# Oscillator_Or_Joystick_Ambisonic_Pan-Rot.net
KiCad netlist of a schematic drawn in EAGLE
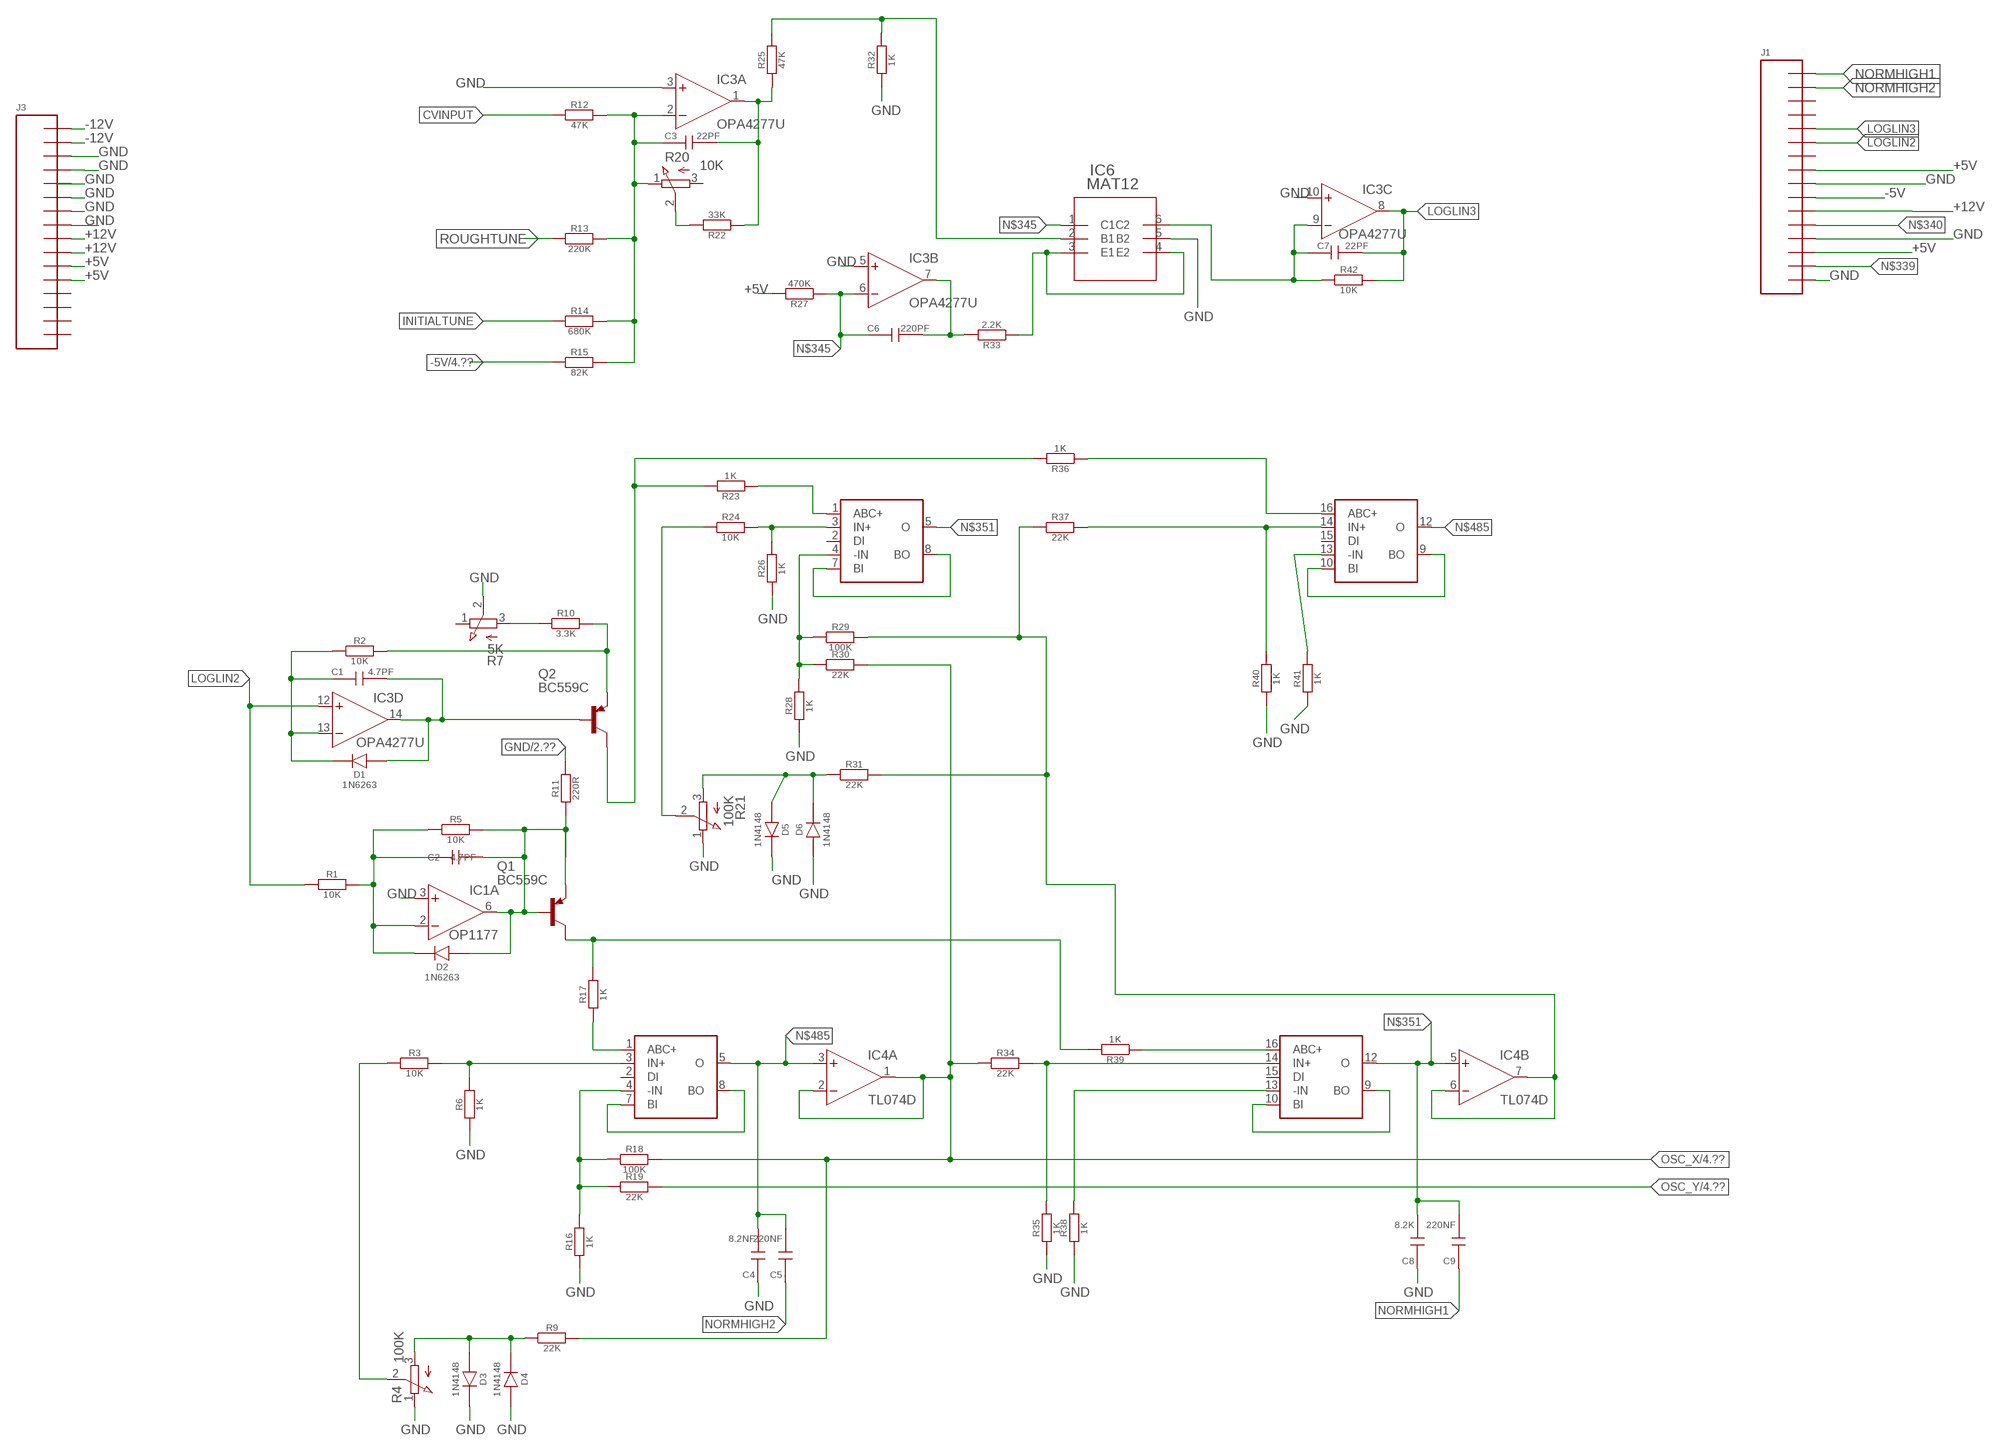
[diagram p0: schematic, sheet 1]
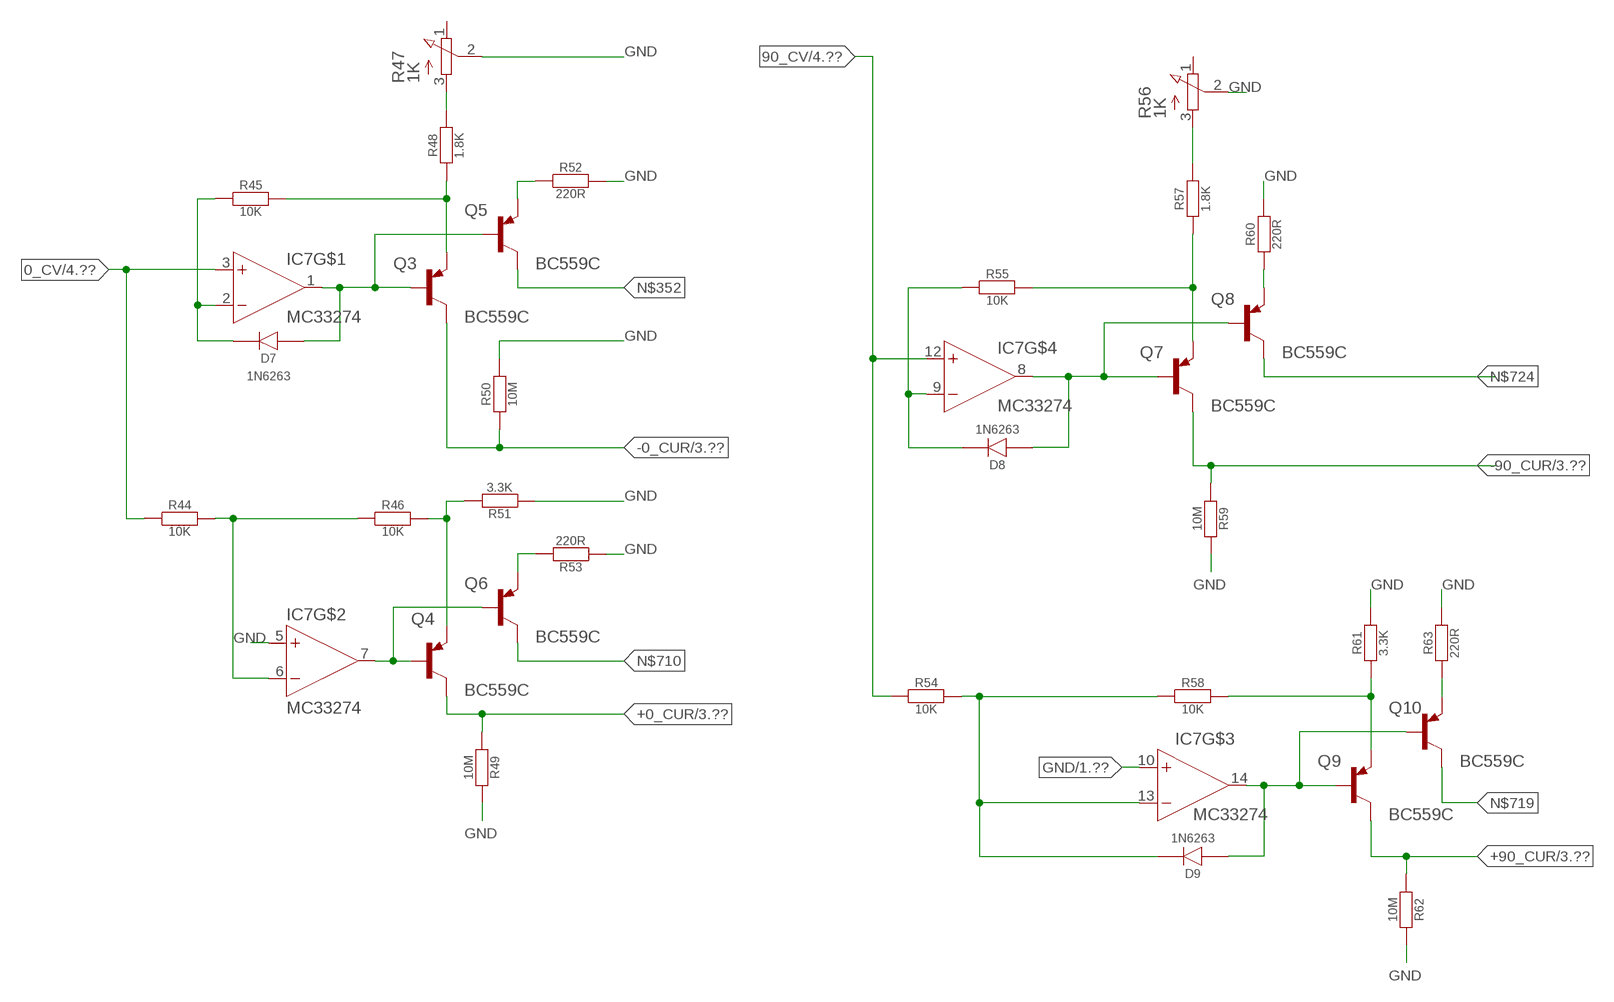
[diagram p1: schematic, sheet 2]
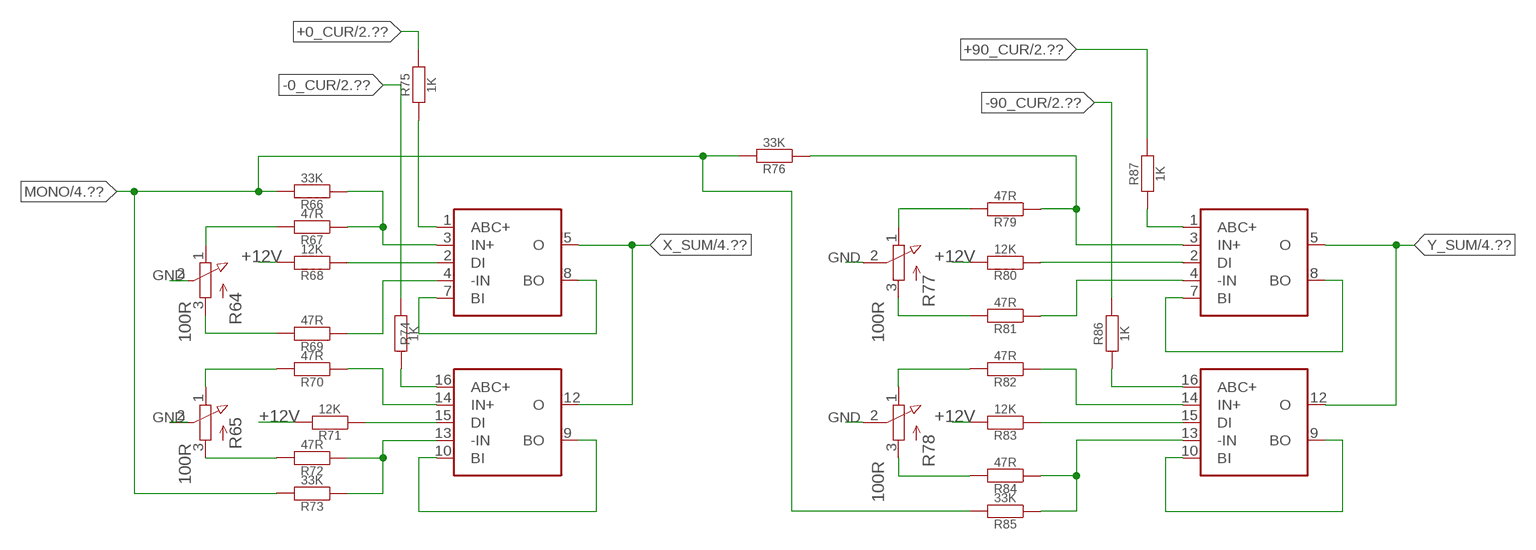
[diagram p2: schematic, sheet 3]
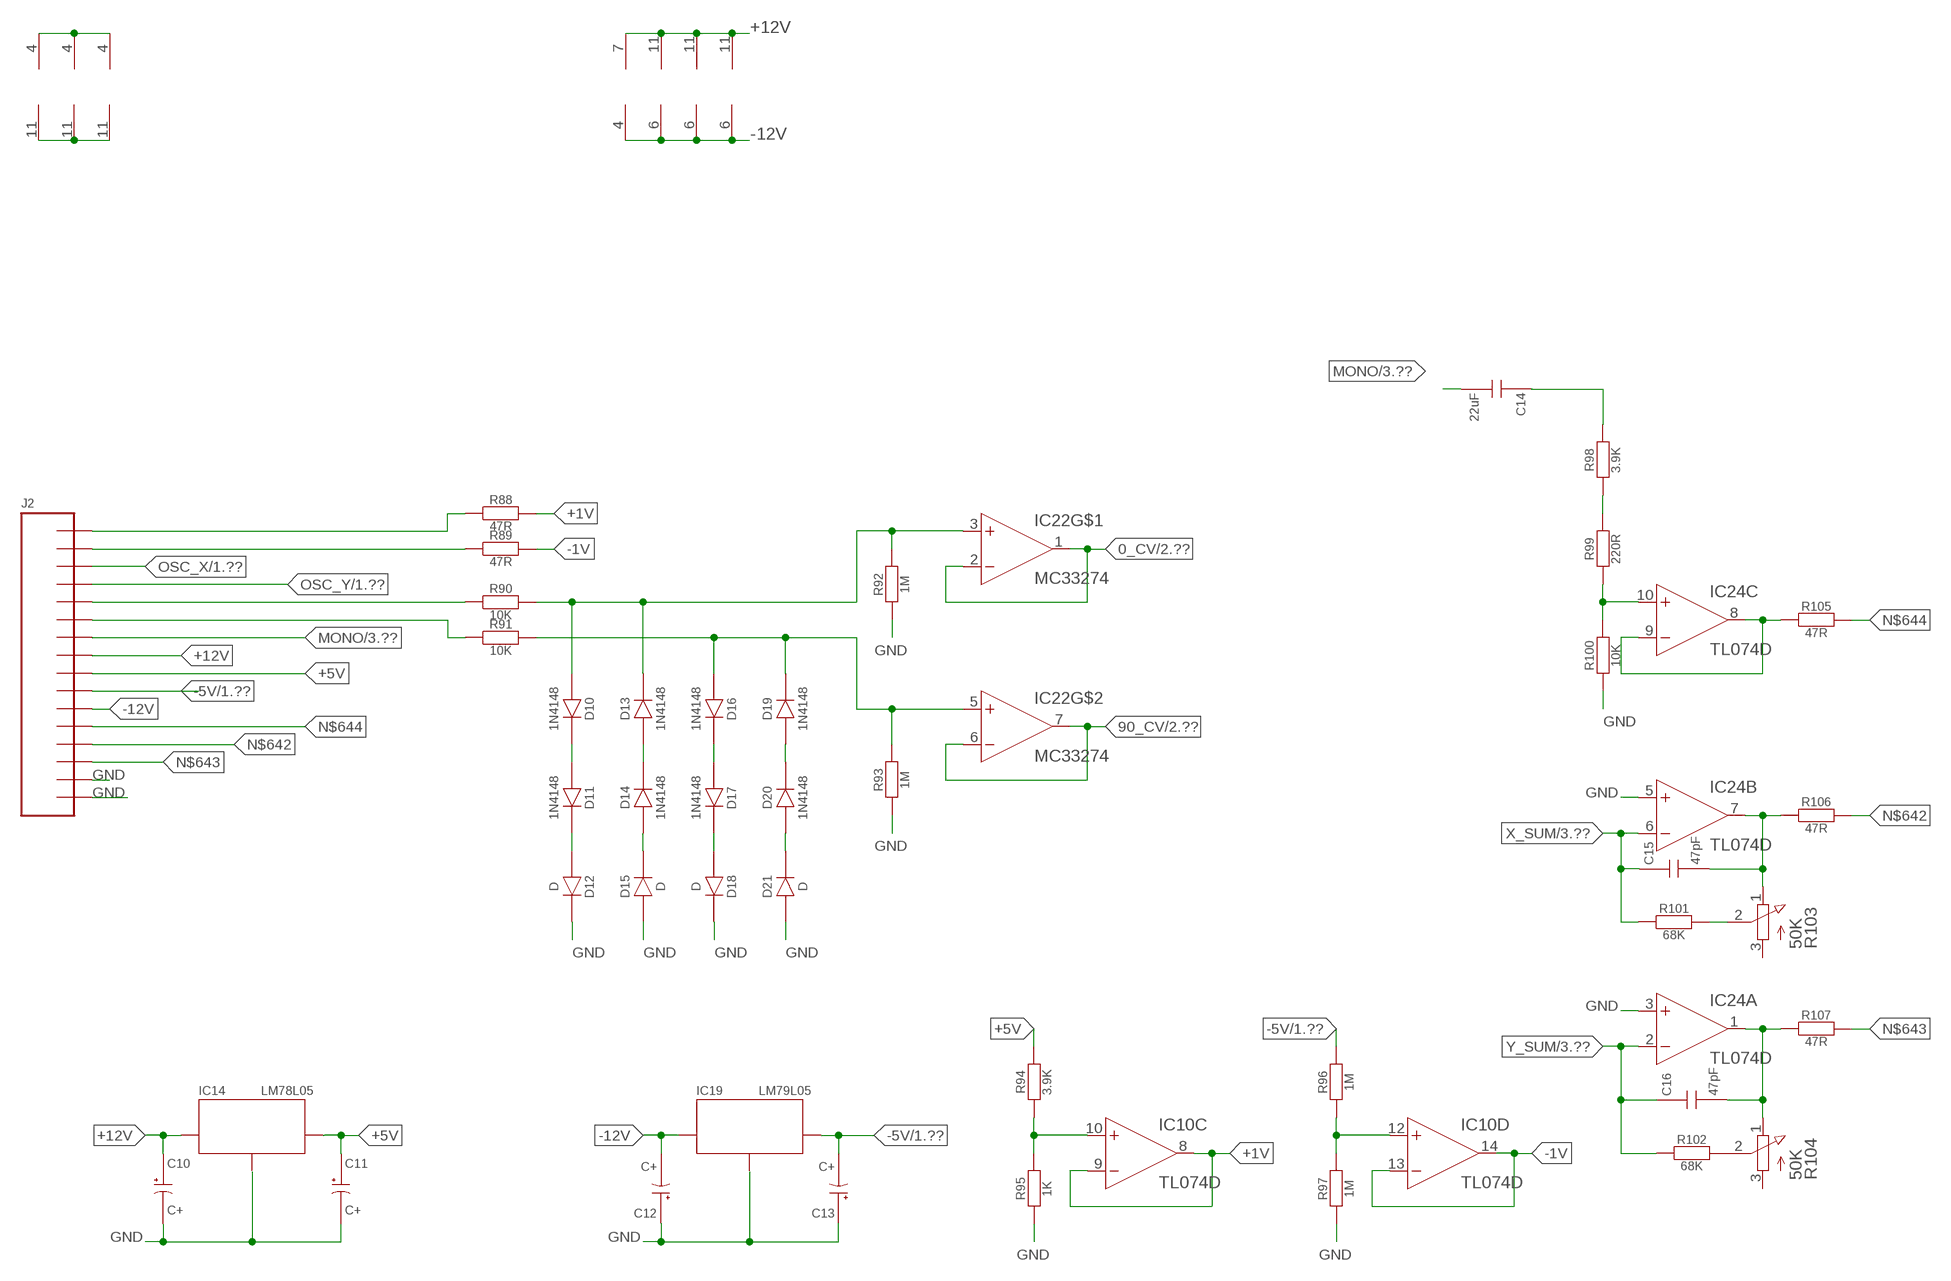
[diagram p3: schematic, sheet 4]

(export (version "E")
  (design (tool "Eeschema 10.0.6"))
  (components
    (comp (ref "C1")
      (value "4.7PF")
      (footprint "eagle-import:CT6032")
      (libsource (lib "eagle-import") (part "C"))
    )
    (comp (ref "C2")
      (value "4.7PF")
      (footprint "eagle-import:CT6032")
      (libsource (lib "eagle-import") (part "C"))
    )
    (comp (ref "C3")
      (value "22PF")
      (footprint "eagle-import:CT6032")
      (libsource (lib "eagle-import") (part "C"))
    )
    (comp (ref "C4")
      (value "8.2NF")
      (footprint "eagle-import:CT6032")
      (libsource (lib "eagle-import") (part "C"))
    )
    (comp (ref "C5")
      (value "220NF")
      (footprint "eagle-import:CT6032")
      (libsource (lib "eagle-import") (part "C"))
    )
    (comp (ref "C6")
      (value "220PF")
      (footprint "eagle-import:CT6032")
      (libsource (lib "eagle-import") (part "C"))
    )
    (comp (ref "C7")
      (value "22PF")
      (footprint "eagle-import:CT6032")
      (libsource (lib "eagle-import") (part "C"))
    )
    (comp (ref "C8")
      (value "8.2K")
      (footprint "eagle-import:CT6032")
      (libsource (lib "eagle-import") (part "C"))
    )
    (comp (ref "C9")
      (value "220NF")
      (footprint "eagle-import:CT6032")
      (libsource (lib "eagle-import") (part "C"))
    )
    (comp (ref "D1")
      (value "1N6263")
      (footprint "eagle-import:SOD123")
      (libsource (lib "eagle-import") (part "D"))
    )
    (comp (ref "D2")
      (value "1N6263")
      (footprint "eagle-import:SOD123")
      (libsource (lib "eagle-import") (part "D"))
    )
    (comp (ref "D3")
      (value "1N4148")
      (footprint "eagle-import:SOD123")
      (libsource (lib "eagle-import") (part "D"))
    )
    (comp (ref "D4")
      (value "1N4148")
      (footprint "eagle-import:SOD123")
      (libsource (lib "eagle-import") (part "D"))
    )
    (comp (ref "D5")
      (value "1N4148")
      (footprint "eagle-import:SOD123")
      (libsource (lib "eagle-import") (part "D"))
    )
    (comp (ref "D6")
      (value "1N4148")
      (footprint "eagle-import:SOD123")
      (libsource (lib "eagle-import") (part "D"))
    )
    (comp (ref "IC1")
      (value "OP1177")
      (footprint "eagle-import:SO08")
      (libsource (lib "eagle-import") (part "OP1177"))
    )
    (comp (ref "IC2")
      (value "LM13700")
      (footprint "eagle-import:SO16")
      (libsource (lib "eagle-import") (part "LM13700"))
    )
    (comp (ref "IC3")
      (value "OPA4277U")
      (footprint "eagle-import:SO14")
      (libsource (lib "eagle-import") (part "OPA4277U"))
    )
    (comp (ref "IC4")
      (value "TL074D")
      (footprint "eagle-import:SO14")
      (libsource (lib "eagle-import") (part "TL074D"))
    )
    (comp (ref "IC5")
      (value "LM13700")
      (footprint "eagle-import:SO16")
      (libsource (lib "eagle-import") (part "LM13700"))
    )
    (comp (ref "IC6")
      (value "MAT12")
      (footprint "eagle-import:H_6")
      (fields (field (name "MANUFACTURER_PART_NUMBER") "MAT12AHZ"))
      (libsource (lib "eagle-import") (part "MAT12"))
    )
    (comp (ref "J1")
      (value "CON_16")
      (footprint "eagle-import:2X08SMT")
      (libsource (lib "eagle-import") (part "CON_16"))
    )
    (comp (ref "J3")
      (value "CON_16")
      (footprint "eagle-import:2X08SMT")
      (libsource (lib "eagle-import") (part "CON_16"))
    )
    (comp (ref "Q1")
      (value "BC559C")
      (footprint "eagle-import:TO92")
      (libsource (lib "eagle-import") (part "BC559C"))
    )
    (comp (ref "Q2")
      (value "BC559C")
      (footprint "eagle-import:TO92")
      (libsource (lib "eagle-import") (part "BC559C"))
    )
    (comp (ref "R1")
      (value "10K")
      (footprint "eagle-import:R6332W")
      (libsource (lib "eagle-import") (part "R"))
    )
    (comp (ref "R2")
      (value "10K")
      (footprint "eagle-import:R6332W")
      (libsource (lib "eagle-import") (part "R"))
    )
    (comp (ref "R3")
      (value "10K")
      (footprint "eagle-import:R6332W")
      (libsource (lib "eagle-import") (part "R"))
    )
    (comp (ref "R4")
      (value "100K")
      (footprint "eagle-import:TRIM")
      (libsource (lib "eagle-import") (part "TRIM"))
    )
    (comp (ref "R5")
      (value "10K")
      (footprint "eagle-import:R6332W")
      (libsource (lib "eagle-import") (part "R"))
    )
    (comp (ref "R6")
      (value "1K")
      (footprint "eagle-import:R6332W")
      (libsource (lib "eagle-import") (part "R"))
    )
    (comp (ref "R7")
      (value "5K")
      (footprint "eagle-import:TRIM")
      (libsource (lib "eagle-import") (part "TRIM"))
    )
    (comp (ref "R9")
      (value "22K")
      (footprint "eagle-import:R6332W")
      (libsource (lib "eagle-import") (part "R"))
    )
    (comp (ref "R10")
      (value "3.3K")
      (footprint "eagle-import:R6332W")
      (libsource (lib "eagle-import") (part "R"))
    )
    (comp (ref "R11")
      (value "220R")
      (footprint "eagle-import:R6332W")
      (libsource (lib "eagle-import") (part "R"))
    )
    (comp (ref "R12")
      (value "47K")
      (footprint "eagle-import:R6332W")
      (libsource (lib "eagle-import") (part "R"))
    )
    (comp (ref "R13")
      (value "220K")
      (footprint "eagle-import:R6332W")
      (libsource (lib "eagle-import") (part "R"))
    )
    (comp (ref "R14")
      (value "680K")
      (footprint "eagle-import:R6332W")
      (libsource (lib "eagle-import") (part "R"))
    )
    (comp (ref "R15")
      (value "82K")
      (footprint "eagle-import:R6332W")
      (libsource (lib "eagle-import") (part "R"))
    )
    (comp (ref "R16")
      (value "1K")
      (footprint "eagle-import:R6332W")
      (libsource (lib "eagle-import") (part "R"))
    )
    (comp (ref "R17")
      (value "1K")
      (footprint "eagle-import:R6332W")
      (libsource (lib "eagle-import") (part "R"))
    )
    (comp (ref "R18")
      (value "100K")
      (footprint "eagle-import:R6332W")
      (libsource (lib "eagle-import") (part "R"))
    )
    (comp (ref "R19")
      (value "22K")
      (footprint "eagle-import:R6332W")
      (libsource (lib "eagle-import") (part "R"))
    )
    (comp (ref "R20")
      (value "10K")
      (footprint "eagle-import:TRIM")
      (libsource (lib "eagle-import") (part "TRIM"))
    )
    (comp (ref "R21")
      (value "100K")
      (footprint "eagle-import:TRIM")
      (libsource (lib "eagle-import") (part "TRIM"))
    )
    (comp (ref "R22")
      (value "33K")
      (footprint "eagle-import:R6332W")
      (libsource (lib "eagle-import") (part "R"))
    )
    (comp (ref "R23")
      (value "1K")
      (footprint "eagle-import:R6332W")
      (libsource (lib "eagle-import") (part "R"))
    )
    (comp (ref "R24")
      (value "10K")
      (footprint "eagle-import:R6332W")
      (libsource (lib "eagle-import") (part "R"))
    )
    (comp (ref "R25")
      (value "47K")
      (footprint "eagle-import:R6332W")
      (libsource (lib "eagle-import") (part "R"))
    )
    (comp (ref "R26")
      (value "1K")
      (footprint "eagle-import:R6332W")
      (libsource (lib "eagle-import") (part "R"))
    )
    (comp (ref "R27")
      (value "470K")
      (footprint "eagle-import:R6332W")
      (libsource (lib "eagle-import") (part "R"))
    )
    (comp (ref "R28")
      (value "1K")
      (footprint "eagle-import:R6332W")
      (libsource (lib "eagle-import") (part "R"))
    )
    (comp (ref "R29")
      (value "100K")
      (footprint "eagle-import:R6332W")
      (libsource (lib "eagle-import") (part "R"))
    )
    (comp (ref "R30")
      (value "22K")
      (footprint "eagle-import:R6332W")
      (libsource (lib "eagle-import") (part "R"))
    )
    (comp (ref "R31")
      (value "22K")
      (footprint "eagle-import:R6332W")
      (libsource (lib "eagle-import") (part "R"))
    )
    (comp (ref "R32")
      (value "1K")
      (footprint "eagle-import:R6332W")
      (libsource (lib "eagle-import") (part "R"))
    )
    (comp (ref "R33")
      (value "2.2K")
      (footprint "eagle-import:R6332W")
      (libsource (lib "eagle-import") (part "R"))
    )
    (comp (ref "R34")
      (value "22K")
      (footprint "eagle-import:R6332W")
      (libsource (lib "eagle-import") (part "R"))
    )
    (comp (ref "R35")
      (value "1K")
      (footprint "eagle-import:R6332W")
      (libsource (lib "eagle-import") (part "R"))
    )
    (comp (ref "R36")
      (value "1K")
      (footprint "eagle-import:R6332W")
      (libsource (lib "eagle-import") (part "R"))
    )
    (comp (ref "R37")
      (value "22K")
      (footprint "eagle-import:R6332W")
      (libsource (lib "eagle-import") (part "R"))
    )
    (comp (ref "R38")
      (value "1K")
      (footprint "eagle-import:R6332W")
      (libsource (lib "eagle-import") (part "R"))
    )
    (comp (ref "R39")
      (value "1K")
      (footprint "eagle-import:R6332W")
      (libsource (lib "eagle-import") (part "R"))
    )
    (comp (ref "R40")
      (value "1K")
      (footprint "eagle-import:R6332W")
      (libsource (lib "eagle-import") (part "R"))
    )
    (comp (ref "R41")
      (value "1K")
      (footprint "eagle-import:R6332W")
      (libsource (lib "eagle-import") (part "R"))
    )
    (comp (ref "R42")
      (value "10K")
      (footprint "eagle-import:R6332W")
      (libsource (lib "eagle-import") (part "R"))
    )
    (comp (ref "D7")
      (value "1N6263")
      (footprint "eagle-import:SOD123")
      (libsource (lib "eagle-import") (part "D"))
    )
    (comp (ref "D8")
      (value "1N6263")
      (footprint "eagle-import:SOD123")
      (libsource (lib "eagle-import") (part "D"))
    )
    (comp (ref "D9")
      (value "1N6263")
      (footprint "eagle-import:SOD123")
      (libsource (lib "eagle-import") (part "D"))
    )
    (comp (ref "IC7")
      (value "MC33274")
      (footprint "eagle-import:SO14")
      (libsource (lib "eagle-import") (part "MC33274"))
    )
    (comp (ref "Q3")
      (value "BC559C")
      (footprint "eagle-import:TO92")
      (libsource (lib "eagle-import") (part "BC559C"))
    )
    (comp (ref "Q4")
      (value "BC559C")
      (footprint "eagle-import:TO92")
      (libsource (lib "eagle-import") (part "BC559C"))
    )
    (comp (ref "Q5")
      (value "BC559C")
      (footprint "eagle-import:TO92")
      (libsource (lib "eagle-import") (part "BC559C"))
    )
    (comp (ref "Q6")
      (value "BC559C")
      (footprint "eagle-import:TO92")
      (libsource (lib "eagle-import") (part "BC559C"))
    )
    (comp (ref "Q7")
      (value "BC559C")
      (footprint "eagle-import:TO92")
      (libsource (lib "eagle-import") (part "BC559C"))
    )
    (comp (ref "Q8")
      (value "BC559C")
      (footprint "eagle-import:TO92")
      (libsource (lib "eagle-import") (part "BC559C"))
    )
    (comp (ref "Q9")
      (value "BC559C")
      (footprint "eagle-import:TO92")
      (libsource (lib "eagle-import") (part "BC559C"))
    )
    (comp (ref "Q10")
      (value "BC559C")
      (footprint "eagle-import:TO92")
      (libsource (lib "eagle-import") (part "BC559C"))
    )
    (comp (ref "R44")
      (value "10K")
      (footprint "eagle-import:R6332W")
      (libsource (lib "eagle-import") (part "R"))
    )
    (comp (ref "R45")
      (value "10K")
      (footprint "eagle-import:R6332W")
      (libsource (lib "eagle-import") (part "R"))
    )
    (comp (ref "R46")
      (value "10K")
      (footprint "eagle-import:R6332W")
      (libsource (lib "eagle-import") (part "R"))
    )
    (comp (ref "R47")
      (value "1K")
      (footprint "eagle-import:TRIM")
      (libsource (lib "eagle-import") (part "TRIM"))
    )
    (comp (ref "R48")
      (value "1.8K")
      (footprint "eagle-import:R6332W")
      (libsource (lib "eagle-import") (part "R"))
    )
    (comp (ref "R49")
      (value "10M")
      (footprint "eagle-import:R6332W")
      (libsource (lib "eagle-import") (part "R"))
    )
    (comp (ref "R50")
      (value "10M")
      (footprint "eagle-import:R6332W")
      (libsource (lib "eagle-import") (part "R"))
    )
    (comp (ref "R51")
      (value "3.3K")
      (footprint "eagle-import:R6332W")
      (libsource (lib "eagle-import") (part "R"))
    )
    (comp (ref "R52")
      (value "220R")
      (footprint "eagle-import:R6332W")
      (libsource (lib "eagle-import") (part "R"))
    )
    (comp (ref "R53")
      (value "220R")
      (footprint "eagle-import:R6332W")
      (libsource (lib "eagle-import") (part "R"))
    )
    (comp (ref "R54")
      (value "10K")
      (footprint "eagle-import:R6332W")
      (libsource (lib "eagle-import") (part "R"))
    )
    (comp (ref "R55")
      (value "10K")
      (footprint "eagle-import:R6332W")
      (libsource (lib "eagle-import") (part "R"))
    )
    (comp (ref "R56")
      (value "1K")
      (footprint "eagle-import:TRIM")
      (libsource (lib "eagle-import") (part "TRIM"))
    )
    (comp (ref "R57")
      (value "1.8K")
      (footprint "eagle-import:R6332W")
      (libsource (lib "eagle-import") (part "R"))
    )
    (comp (ref "R58")
      (value "10K")
      (footprint "eagle-import:R6332W")
      (libsource (lib "eagle-import") (part "R"))
    )
    (comp (ref "R59")
      (value "10M")
      (footprint "eagle-import:R6332W")
      (libsource (lib "eagle-import") (part "R"))
    )
    (comp (ref "R60")
      (value "220R")
      (footprint "eagle-import:R6332W")
      (libsource (lib "eagle-import") (part "R"))
    )
    (comp (ref "R61")
      (value "3.3K")
      (footprint "eagle-import:R6332W")
      (libsource (lib "eagle-import") (part "R"))
    )
    (comp (ref "R62")
      (value "10M")
      (footprint "eagle-import:R6332W")
      (libsource (lib "eagle-import") (part "R"))
    )
    (comp (ref "R63")
      (value "220R")
      (footprint "eagle-import:R6332W")
      (libsource (lib "eagle-import") (part "R"))
    )
    (comp (ref "IC8")
      (value "LM13700")
      (footprint "eagle-import:SO16")
      (libsource (lib "eagle-import") (part "LM13700"))
    )
    (comp (ref "IC9")
      (value "LM13700")
      (footprint "eagle-import:SO16")
      (libsource (lib "eagle-import") (part "LM13700"))
    )
    (comp (ref "R64")
      (value "100R")
      (footprint "eagle-import:TRIM")
      (libsource (lib "eagle-import") (part "TRIM"))
    )
    (comp (ref "R65")
      (value "100R")
      (footprint "eagle-import:TRIM")
      (libsource (lib "eagle-import") (part "TRIM"))
    )
    (comp (ref "R66")
      (value "33K")
      (footprint "eagle-import:R6332W")
      (libsource (lib "eagle-import") (part "R"))
    )
    (comp (ref "R67")
      (value "47R")
      (footprint "eagle-import:R6332W")
      (libsource (lib "eagle-import") (part "R"))
    )
    (comp (ref "R68")
      (value "12K")
      (footprint "eagle-import:R6332W")
      (libsource (lib "eagle-import") (part "R"))
    )
    (comp (ref "R69")
      (value "47R")
      (footprint "eagle-import:R6332W")
      (libsource (lib "eagle-import") (part "R"))
    )
    (comp (ref "R70")
      (value "47R")
      (footprint "eagle-import:R6332W")
      (libsource (lib "eagle-import") (part "R"))
    )
    (comp (ref "R71")
      (value "12K")
      (footprint "eagle-import:R6332W")
      (libsource (lib "eagle-import") (part "R"))
    )
    (comp (ref "R72")
      (value "47R")
      (footprint "eagle-import:R6332W")
      (libsource (lib "eagle-import") (part "R"))
    )
    (comp (ref "R73")
      (value "33K")
      (footprint "eagle-import:R6332W")
      (libsource (lib "eagle-import") (part "R"))
    )
    (comp (ref "R74")
      (value "1K")
      (footprint "eagle-import:R6332W")
      (libsource (lib "eagle-import") (part "R"))
    )
    (comp (ref "R75")
      (value "1K")
      (footprint "eagle-import:R6332W")
      (libsource (lib "eagle-import") (part "R"))
    )
    (comp (ref "R76")
      (value "33K")
      (footprint "eagle-import:R6332W")
      (libsource (lib "eagle-import") (part "R"))
    )
    (comp (ref "R77")
      (value "100R")
      (footprint "eagle-import:TRIM")
      (libsource (lib "eagle-import") (part "TRIM"))
    )
    (comp (ref "R78")
      (value "100R")
      (footprint "eagle-import:TRIM")
      (libsource (lib "eagle-import") (part "TRIM"))
    )
    (comp (ref "R79")
      (value "47R")
      (footprint "eagle-import:R6332W")
      (libsource (lib "eagle-import") (part "R"))
    )
    (comp (ref "R80")
      (value "12K")
      (footprint "eagle-import:R6332W")
      (libsource (lib "eagle-import") (part "R"))
    )
    (comp (ref "R81")
      (value "47R")
      (footprint "eagle-import:R6332W")
      (libsource (lib "eagle-import") (part "R"))
    )
    (comp (ref "R82")
      (value "47R")
      (footprint "eagle-import:R6332W")
      (libsource (lib "eagle-import") (part "R"))
    )
    (comp (ref "R83")
      (value "12K")
      (footprint "eagle-import:R6332W")
      (libsource (lib "eagle-import") (part "R"))
    )
    (comp (ref "R84")
      (value "47R")
      (footprint "eagle-import:R6332W")
      (libsource (lib "eagle-import") (part "R"))
    )
    (comp (ref "R85")
      (value "33K")
      (footprint "eagle-import:R6332W")
      (libsource (lib "eagle-import") (part "R"))
    )
    (comp (ref "R86")
      (value "1K")
      (footprint "eagle-import:R6332W")
      (libsource (lib "eagle-import") (part "R"))
    )
    (comp (ref "R87")
      (value "1K")
      (footprint "eagle-import:R6332W")
      (libsource (lib "eagle-import") (part "R"))
    )
    (comp (ref "C10")
      (value "C+")
      (footprint "eagle-import:PANASONIC_E")
      (libsource (lib "eagle-import") (part "C+"))
    )
    (comp (ref "C11")
      (value "C+")
      (footprint "eagle-import:PANASONIC_E")
      (libsource (lib "eagle-import") (part "C+"))
    )
    (comp (ref "C12")
      (value "C+")
      (footprint "eagle-import:PANASONIC_E")
      (libsource (lib "eagle-import") (part "C+"))
    )
    (comp (ref "C13")
      (value "C+")
      (footprint "eagle-import:PANASONIC_E")
      (libsource (lib "eagle-import") (part "C+"))
    )
    (comp (ref "C14")
      (value "22uF")
      (footprint "eagle-import:CT6032")
      (libsource (lib "eagle-import") (part "C"))
    )
    (comp (ref "C15")
      (value "47pF")
      (footprint "eagle-import:CT6032")
      (libsource (lib "eagle-import") (part "C"))
    )
    (comp (ref "C16")
      (value "47pF")
      (footprint "eagle-import:CT6032")
      (libsource (lib "eagle-import") (part "C"))
    )
    (comp (ref "D10")
      (value "1N4148")
      (footprint "eagle-import:SOD123")
      (libsource (lib "eagle-import") (part "D"))
    )
    (comp (ref "D11")
      (value "1N4148")
      (footprint "eagle-import:SOD123")
      (libsource (lib "eagle-import") (part "D"))
    )
    (comp (ref "D12")
      (value "D")
      (footprint "eagle-import:SOD123")
      (libsource (lib "eagle-import") (part "D"))
    )
    (comp (ref "D13")
      (value "1N4148")
      (footprint "eagle-import:SOD123")
      (libsource (lib "eagle-import") (part "D"))
    )
    (comp (ref "D14")
      (value "1N4148")
      (footprint "eagle-import:SOD123")
      (libsource (lib "eagle-import") (part "D"))
    )
    (comp (ref "D15")
      (value "D")
      (footprint "eagle-import:SOD123")
      (libsource (lib "eagle-import") (part "D"))
    )
    (comp (ref "D16")
      (value "1N4148")
      (footprint "eagle-import:SOD123")
      (libsource (lib "eagle-import") (part "D"))
    )
    (comp (ref "D17")
      (value "1N4148")
      (footprint "eagle-import:SOD123")
      (libsource (lib "eagle-import") (part "D"))
    )
    (comp (ref "D18")
      (value "D")
      (footprint "eagle-import:SOD123")
      (libsource (lib "eagle-import") (part "D"))
    )
    (comp (ref "D19")
      (value "1N4148")
      (footprint "eagle-import:SOD123")
      (libsource (lib "eagle-import") (part "D"))
    )
    (comp (ref "D20")
      (value "1N4148")
      (footprint "eagle-import:SOD123")
      (libsource (lib "eagle-import") (part "D"))
    )
    (comp (ref "D21")
      (value "D")
      (footprint "eagle-import:SOD123")
      (libsource (lib "eagle-import") (part "D"))
    )
    (comp (ref "IC10")
      (value "TL074D")
      (footprint "eagle-import:SO14")
      (libsource (lib "eagle-import") (part "TL074D"))
    )
    (comp (ref "IC14")
      (value "LM78L05")
      (footprint "eagle-import:SO08")
      (libsource (lib "eagle-import") (part "VREG"))
    )
    (comp (ref "IC19")
      (value "LM79L05")
      (footprint "eagle-import:SO08")
      (libsource (lib "eagle-import") (part "VREG"))
    )
    (comp (ref "IC22")
      (value "MC33274")
      (footprint "eagle-import:SO14")
      (libsource (lib "eagle-import") (part "MC33274"))
    )
    (comp (ref "IC24")
      (value "TL074D")
      (footprint "eagle-import:SO14")
      (libsource (lib "eagle-import") (part "TL074D"))
    )
    (comp (ref "J2")
      (value "CON_16")
      (footprint "eagle-import:2X08SMT")
      (libsource (lib "eagle-import") (part "CON_16"))
    )
    (comp (ref "R88")
      (value "47R")
      (footprint "eagle-import:R6332W")
      (libsource (lib "eagle-import") (part "R"))
    )
    (comp (ref "R89")
      (value "47R")
      (footprint "eagle-import:R6332W")
      (libsource (lib "eagle-import") (part "R"))
    )
    (comp (ref "R90")
      (value "10K")
      (footprint "eagle-import:R6332W")
      (libsource (lib "eagle-import") (part "R"))
    )
    (comp (ref "R91")
      (value "10K")
      (footprint "eagle-import:R6332W")
      (libsource (lib "eagle-import") (part "R"))
    )
    (comp (ref "R92")
      (value "1M")
      (footprint "eagle-import:R6332W")
      (libsource (lib "eagle-import") (part "R"))
    )
    (comp (ref "R93")
      (value "1M")
      (footprint "eagle-import:R6332W")
      (libsource (lib "eagle-import") (part "R"))
    )
    (comp (ref "R94")
      (value "3.9K")
      (footprint "eagle-import:R6332W")
      (libsource (lib "eagle-import") (part "R"))
    )
    (comp (ref "R95")
      (value "1K")
      (footprint "eagle-import:R6332W")
      (libsource (lib "eagle-import") (part "R"))
    )
    (comp (ref "R96")
      (value "1M")
      (footprint "eagle-import:R6332W")
      (libsource (lib "eagle-import") (part "R"))
    )
    (comp (ref "R97")
      (value "1M")
      (footprint "eagle-import:R6332W")
      (libsource (lib "eagle-import") (part "R"))
    )
    (comp (ref "R98")
      (value "3.9K")
      (footprint "eagle-import:R6332W")
      (libsource (lib "eagle-import") (part "R"))
    )
    (comp (ref "R99")
      (value "220R")
      (footprint "eagle-import:R6332W")
      (libsource (lib "eagle-import") (part "R"))
    )
    (comp (ref "R100")
      (value "10K")
      (footprint "eagle-import:R6332W")
      (libsource (lib "eagle-import") (part "R"))
    )
    (comp (ref "R101")
      (value "68K")
      (footprint "eagle-import:R6332W")
      (libsource (lib "eagle-import") (part "R"))
    )
    (comp (ref "R102")
      (value "68K")
      (footprint "eagle-import:R6332W")
      (libsource (lib "eagle-import") (part "R"))
    )
    (comp (ref "R103")
      (value "50K")
      (footprint "eagle-import:TRIM")
      (libsource (lib "eagle-import") (part "TRIM"))
    )
    (comp (ref "R104")
      (value "50K")
      (footprint "eagle-import:TRIM")
      (libsource (lib "eagle-import") (part "TRIM"))
    )
    (comp (ref "R105")
      (value "47R")
      (footprint "eagle-import:R6332W")
      (libsource (lib "eagle-import") (part "R"))
    )
    (comp (ref "R106")
      (value "47R")
      (footprint "eagle-import:R6332W")
      (libsource (lib "eagle-import") (part "R"))
    )
    (comp (ref "R107")
      (value "47R")
      (footprint "eagle-import:R6332W")
      (libsource (lib "eagle-import") (part "R"))
    )
  )
  (nets
    (net (code "1") (name "+0_CUR") (class "Default")
      (node (ref "Q4") (pin "C") (pinfunction "C_C") (pintype "passive"))
      (node (ref "R49") (pin "1") (pinfunction "1_1") (pintype "passive"))
      (node (ref "R75") (pin "2") (pinfunction "2_2") (pintype "passive"))
    )
    (net (code "2") (name "+1V") (class "Default")
      (node (ref "IC10") (pin "8") (pinfunction "OUT_8") (pintype "output"))
      (node (ref "IC10") (pin "9") (pinfunction "-IN_9") (pintype "input"))
      (node (ref "R88") (pin "2") (pinfunction "2_2") (pintype "passive"))
    )
    (net (code "3") (name "+5V") (class "Default")
      (node (ref "C11") (pin "+") (pinfunction "1_+") (pintype "passive"))
      (node (ref "IC14") (pin "1") (pinfunction "OUT_1") (pintype "passive"))
      (node (ref "J1") (pin "14") (pinfunction "14_14") (pintype "bidirectional"))
      (node (ref "J1") (pin "8") (pinfunction "8_8") (pintype "bidirectional"))
      (node (ref "J2") (pin "9") (pinfunction "9_9") (pintype "bidirectional"))
      (node (ref "J3") (pin "11") (pinfunction "11_11") (pintype "bidirectional"))
      (node (ref "J3") (pin "12") (pinfunction "12_12") (pintype "bidirectional"))
      (node (ref "R27") (pin "2") (pinfunction "2_2") (pintype "passive"))
      (node (ref "R94") (pin "2") (pinfunction "2_2") (pintype "passive"))
    )
    (net (code "4") (name "+12V") (class "Default")
      (node (ref "C10") (pin "+") (pinfunction "1_+") (pintype "passive"))
      (node (ref "IC1") (pin "7") (pinfunction "V+_7") (pintype "power_in"))
      (node (ref "IC14") (pin "8") (pinfunction "IN_8") (pintype "input"))
      (node (ref "IC24") (pin "4") (pinfunction "V+_4") (pintype "power_in"))
      (node (ref "IC3") (pin "4") (pinfunction "V+_4") (pintype "power_in"))
      (node (ref "IC5") (pin "11") (pinfunction "V+_11") (pintype "power_in"))
      (node (ref "IC7") (pin "4") (pinfunction "V+_4") (pintype "power_in"))
      (node (ref "IC8") (pin "11") (pinfunction "V+_11") (pintype "power_in"))
      (node (ref "IC9") (pin "11") (pinfunction "V+_11") (pintype "power_in"))
      (node (ref "J1") (pin "11") (pinfunction "11_11") (pintype "bidirectional"))
      (node (ref "J2") (pin "8") (pinfunction "8_8") (pintype "bidirectional"))
      (node (ref "J3") (pin "10") (pinfunction "10_10") (pintype "bidirectional"))
      (node (ref "J3") (pin "9") (pinfunction "9_9") (pintype "bidirectional"))
      (node (ref "R68") (pin "2") (pinfunction "2_2") (pintype "passive"))
      (node (ref "R71") (pin "2") (pinfunction "2_2") (pintype "passive"))
      (node (ref "R80") (pin "2") (pinfunction "2_2") (pintype "passive"))
      (node (ref "R83") (pin "2") (pinfunction "2_2") (pintype "passive"))
    )
    (net (code "5") (name "+90_CUR") (class "Default")
      (node (ref "Q9") (pin "C") (pinfunction "C_C") (pintype "passive"))
      (node (ref "R62") (pin "1") (pinfunction "1_1") (pintype "passive"))
      (node (ref "R87") (pin "2") (pinfunction "2_2") (pintype "passive"))
    )
    (net (code "6") (name "-0_CUR") (class "Default")
      (node (ref "Q3") (pin "C") (pinfunction "C_C") (pintype "passive"))
      (node (ref "R50") (pin "1") (pinfunction "1_1") (pintype "passive"))
      (node (ref "R74") (pin "2") (pinfunction "2_2") (pintype "passive"))
    )
    (net (code "7") (name "-1V") (class "Default")
      (node (ref "IC10") (pin "13") (pinfunction "-IN_13") (pintype "input"))
      (node (ref "IC10") (pin "14") (pinfunction "OUT_14") (pintype "output"))
      (node (ref "R89") (pin "2") (pinfunction "2_2") (pintype "passive"))
    )
    (net (code "8") (name "-5V") (class "Default")
      (node (ref "C13") (pin "-") (pinfunction "2_-") (pintype "passive"))
      (node (ref "IC19") (pin "1") (pinfunction "OUT_1") (pintype "passive"))
      (node (ref "J1") (pin "10") (pinfunction "10_10") (pintype "bidirectional"))
      (node (ref "J2") (pin "10") (pinfunction "10_10") (pintype "bidirectional"))
      (node (ref "R15") (pin "1") (pinfunction "1_1") (pintype "passive"))
      (node (ref "R96") (pin "2") (pinfunction "2_2") (pintype "passive"))
    )
    (net (code "9") (name "-12V") (class "Default")
      (node (ref "C12") (pin "-") (pinfunction "2_-") (pintype "passive"))
      (node (ref "IC1") (pin "4") (pinfunction "V-_4") (pintype "power_in"))
      (node (ref "IC19") (pin "8") (pinfunction "IN_8") (pintype "input"))
      (node (ref "IC24") (pin "11") (pinfunction "V-_11") (pintype "power_in"))
      (node (ref "IC3") (pin "11") (pinfunction "V-_11") (pintype "power_in"))
      (node (ref "IC5") (pin "6") (pinfunction "V-_6") (pintype "power_in"))
      (node (ref "IC7") (pin "11") (pinfunction "V-_11") (pintype "power_in"))
      (node (ref "IC8") (pin "6") (pinfunction "V-_6") (pintype "power_in"))
      (node (ref "IC9") (pin "6") (pinfunction "V-_6") (pintype "power_in"))
      (node (ref "J2") (pin "11") (pinfunction "11_11") (pintype "bidirectional"))
      (node (ref "J3") (pin "1") (pinfunction "1_1") (pintype "bidirectional"))
      (node (ref "J3") (pin "2") (pinfunction "2_2") (pintype "bidirectional"))
    )
    (net (code "10") (name "-90_CUR") (class "Default")
      (node (ref "Q7") (pin "C") (pinfunction "C_C") (pintype "passive"))
      (node (ref "R59") (pin "1") (pinfunction "1_1") (pintype "passive"))
      (node (ref "R86") (pin "2") (pinfunction "2_2") (pintype "passive"))
    )
    (net (code "11") (name "0_CV") (class "Default")
      (node (ref "IC22") (pin "1") (pinfunction "OUT_1") (pintype "output"))
      (node (ref "IC22") (pin "2") (pinfunction "-IN_2") (pintype "input"))
      (node (ref "IC7") (pin "3") (pinfunction "+IN_3") (pintype "input"))
      (node (ref "R44") (pin "1") (pinfunction "1_1") (pintype "passive"))
    )
    (net (code "12") (name "90_CV") (class "Default")
      (node (ref "IC22") (pin "6") (pinfunction "-IN_6") (pintype "input"))
      (node (ref "IC22") (pin "7") (pinfunction "OUT_7") (pintype "output"))
      (node (ref "IC7") (pin "12") (pinfunction "+IN_12") (pintype "input"))
      (node (ref "R54") (pin "1") (pinfunction "1_1") (pintype "passive"))
    )
    (net (code "13") (name "CVINPUT") (class "Default")
      (node (ref "R12") (pin "1") (pinfunction "1_1") (pintype "passive"))
    )
    (net (code "14") (name "GND") (class "Default")
      (node (ref "C10") (pin "-") (pinfunction "2_-") (pintype "passive"))
      (node (ref "C11") (pin "-") (pinfunction "2_-") (pintype "passive"))
      (node (ref "C12") (pin "+") (pinfunction "1_+") (pintype "passive"))
      (node (ref "C13") (pin "+") (pinfunction "1_+") (pintype "passive"))
      (node (ref "C4") (pin "+") (pinfunction "1_+") (pintype "passive"))
      (node (ref "C8") (pin "+") (pinfunction "1_+") (pintype "passive"))
      (node (ref "D12") (pin "C") (pinfunction "C_C") (pintype "passive"))
      (node (ref "D15") (pin "A") (pinfunction "A_A") (pintype "passive"))
      (node (ref "D18") (pin "C") (pinfunction "C_C") (pintype "passive"))
      (node (ref "D21") (pin "A") (pinfunction "A_A") (pintype "passive"))
      (node (ref "D3") (pin "C") (pinfunction "C_C") (pintype "passive"))
      (node (ref "D4") (pin "A") (pinfunction "A_A") (pintype "passive"))
      (node (ref "D5") (pin "C") (pinfunction "C_C") (pintype "passive"))
      (node (ref "D6") (pin "A") (pinfunction "A_A") (pintype "passive"))
      (node (ref "IC1") (pin "3") (pinfunction "+IN_3") (pintype "input"))
      (node (ref "IC14") (pin "2") (pinfunction "GND_2") (pintype "input"))
      (node (ref "IC14") (pin "3") (pinfunction "GND_3") (pintype "input"))
      (node (ref "IC14") (pin "6") (pinfunction "GND_6") (pintype "input"))
      (node (ref "IC14") (pin "7") (pinfunction "GND_7") (pintype "input"))
      (node (ref "IC19") (pin "2") (pinfunction "GND_2") (pintype "input"))
      (node (ref "IC19") (pin "3") (pinfunction "GND_3") (pintype "input"))
      (node (ref "IC19") (pin "6") (pinfunction "GND_6") (pintype "input"))
      (node (ref "IC19") (pin "7") (pinfunction "GND_7") (pintype "input"))
      (node (ref "IC24") (pin "3") (pinfunction "+IN_3") (pintype "input"))
      (node (ref "IC24") (pin "5") (pinfunction "+IN_5") (pintype "input"))
      (node (ref "IC3") (pin "10") (pinfunction "+IN_10") (pintype "input"))
      (node (ref "IC3") (pin "3") (pinfunction "+IN_3") (pintype "input"))
      (node (ref "IC3") (pin "5") (pinfunction "+IN_5") (pintype "input"))
      (node (ref "IC6") (pin "5") (pinfunction "B2_5") (pintype "passive"))
      (node (ref "IC7") (pin "10") (pinfunction "+IN_10") (pintype "input"))
      (node (ref "IC7") (pin "5") (pinfunction "+IN_5") (pintype "input"))
      (node (ref "J1") (pin "13") (pinfunction "13_13") (pintype "bidirectional"))
      (node (ref "J1") (pin "16") (pinfunction "16_16") (pintype "bidirectional"))
      (node (ref "J1") (pin "9") (pinfunction "9_9") (pintype "bidirectional"))
      (node (ref "J2") (pin "15") (pinfunction "15_15") (pintype "bidirectional"))
      (node (ref "J2") (pin "16") (pinfunction "16_16") (pintype "bidirectional"))
      (node (ref "J3") (pin "3") (pinfunction "3_3") (pintype "bidirectional"))
      (node (ref "J3") (pin "4") (pinfunction "4_4") (pintype "bidirectional"))
      (node (ref "J3") (pin "5") (pinfunction "5_5") (pintype "bidirectional"))
      (node (ref "J3") (pin "6") (pinfunction "6_6") (pintype "bidirectional"))
      (node (ref "J3") (pin "7") (pinfunction "7_7") (pintype "bidirectional"))
      (node (ref "J3") (pin "8") (pinfunction "8_8") (pintype "bidirectional"))
      (node (ref "R100") (pin "1") (pinfunction "1_1") (pintype "passive"))
      (node (ref "R11") (pin "2") (pinfunction "2_2") (pintype "passive"))
      (node (ref "R16") (pin "1") (pinfunction "1_1") (pintype "passive"))
      (node (ref "R21") (pin "1") (pinfunction "A_1") (pintype "passive"))
      (node (ref "R26") (pin "1") (pinfunction "1_1") (pintype "passive"))
      (node (ref "R28") (pin "1") (pinfunction "1_1") (pintype "passive"))
      (node (ref "R32") (pin "1") (pinfunction "1_1") (pintype "passive"))
      (node (ref "R35") (pin "1") (pinfunction "1_1") (pintype "passive"))
      (node (ref "R38") (pin "1") (pinfunction "1_1") (pintype "passive"))
      (node (ref "R4") (pin "1") (pinfunction "A_1") (pintype "passive"))
      (node (ref "R40") (pin "1") (pinfunction "1_1") (pintype "passive"))
      (node (ref "R41") (pin "1") (pinfunction "1_1") (pintype "passive"))
      (node (ref "R47") (pin "2") (pinfunction "E_2") (pintype "passive"))
      (node (ref "R49") (pin "2") (pinfunction "2_2") (pintype "passive"))
      (node (ref "R50") (pin "2") (pinfunction "2_2") (pintype "passive"))
      (node (ref "R51") (pin "1") (pinfunction "1_1") (pintype "passive"))
      (node (ref "R52") (pin "2") (pinfunction "2_2") (pintype "passive"))
      (node (ref "R53") (pin "1") (pinfunction "1_1") (pintype "passive"))
      (node (ref "R56") (pin "2") (pinfunction "E_2") (pintype "passive"))
      (node (ref "R59") (pin "2") (pinfunction "2_2") (pintype "passive"))
      (node (ref "R6") (pin "1") (pinfunction "1_1") (pintype "passive"))
      (node (ref "R60") (pin "2") (pinfunction "2_2") (pintype "passive"))
      (node (ref "R61") (pin "2") (pinfunction "2_2") (pintype "passive"))
      (node (ref "R62") (pin "2") (pinfunction "2_2") (pintype "passive"))
      (node (ref "R63") (pin "2") (pinfunction "2_2") (pintype "passive"))
      (node (ref "R64") (pin "2") (pinfunction "E_2") (pintype "passive"))
      (node (ref "R65") (pin "2") (pinfunction "E_2") (pintype "passive"))
      (node (ref "R7") (pin "2") (pinfunction "E_2") (pintype "passive"))
      (node (ref "R77") (pin "2") (pinfunction "E_2") (pintype "passive"))
      (node (ref "R78") (pin "2") (pinfunction "E_2") (pintype "passive"))
      (node (ref "R92") (pin "1") (pinfunction "1_1") (pintype "passive"))
      (node (ref "R93") (pin "1") (pinfunction "1_1") (pintype "passive"))
      (node (ref "R95") (pin "1") (pinfunction "1_1") (pintype "passive"))
      (node (ref "R97") (pin "1") (pinfunction "1_1") (pintype "passive"))
    )
    (net (code "15") (name "INITIALTUNE") (class "Default")
      (node (ref "R14") (pin "1") (pinfunction "1_1") (pintype "passive"))
    )
    (net (code "16") (name "LOGLIN2") (class "Default")
      (node (ref "IC3") (pin "12") (pinfunction "+IN_12") (pintype "input"))
      (node (ref "J1") (pin "6") (pinfunction "6_6") (pintype "bidirectional"))
      (node (ref "R1") (pin "1") (pinfunction "1_1") (pintype "passive"))
    )
    (net (code "17") (name "LOGLIN3") (class "Default")
      (node (ref "C7") (pin "-") (pinfunction "2_-") (pintype "passive"))
      (node (ref "IC3") (pin "8") (pinfunction "OUT_8") (pintype "output"))
      (node (ref "J1") (pin "5") (pinfunction "5_5") (pintype "bidirectional"))
      (node (ref "R42") (pin "2") (pinfunction "2_2") (pintype "passive"))
    )
    (net (code "18") (name "MONO") (class "Default")
      (node (ref "C14") (pin "-") (pinfunction "2_-") (pintype "passive"))
      (node (ref "J2") (pin "7") (pinfunction "7_7") (pintype "bidirectional"))
      (node (ref "R66") (pin "2") (pinfunction "2_2") (pintype "passive"))
      (node (ref "R73") (pin "2") (pinfunction "2_2") (pintype "passive"))
      (node (ref "R76") (pin "2") (pinfunction "2_2") (pintype "passive"))
      (node (ref "R85") (pin "2") (pinfunction "2_2") (pintype "passive"))
    )
    (net (code "19") (name "N$339") (class "Default")
      (node (ref "J1") (pin "15") (pinfunction "15_15") (pintype "bidirectional"))
    )
    (net (code "20") (name "N$340") (class "Default")
      (node (ref "J1") (pin "12") (pinfunction "12_12") (pintype "bidirectional"))
    )
    (net (code "21") (name "N$345") (class "Default")
      (node (ref "C6") (pin "+") (pinfunction "1_+") (pintype "passive"))
      (node (ref "IC3") (pin "6") (pinfunction "-IN_6") (pintype "input"))
      (node (ref "IC6") (pin "1") (pinfunction "C1_1") (pintype "passive"))
      (node (ref "R27") (pin "1") (pinfunction "1_1") (pintype "passive"))
    )
    (net (code "22") (name "N$351") (class "Default")
      (node (ref "C8") (pin "-") (pinfunction "2_-") (pintype "passive"))
      (node (ref "C9") (pin "-") (pinfunction "2_-") (pintype "passive"))
      (node (ref "IC2") (pin "12") (pinfunction "O_12") (pintype "bidirectional"))
      (node (ref "IC4") (pin "5") (pinfunction "+IN_5") (pintype "input"))
      (node (ref "IC5") (pin "5") (pinfunction "O_5") (pintype "bidirectional"))
    )
    (net (code "23") (name "N$352") (class "Default")
      (node (ref "Q5") (pin "C") (pinfunction "C_C") (pintype "passive"))
    )
    (net (code "24") (name "N$485") (class "Default")
      (node (ref "C4") (pin "-") (pinfunction "2_-") (pintype "passive"))
      (node (ref "C5") (pin "-") (pinfunction "2_-") (pintype "passive"))
      (node (ref "IC2") (pin "5") (pinfunction "O_5") (pintype "bidirectional"))
      (node (ref "IC4") (pin "3") (pinfunction "+IN_3") (pintype "input"))
      (node (ref "IC5") (pin "12") (pinfunction "O_12") (pintype "bidirectional"))
    )
    (net (code "25") (name "N$642") (class "Default")
      (node (ref "J2") (pin "13") (pinfunction "13_13") (pintype "bidirectional"))
      (node (ref "R106") (pin "2") (pinfunction "2_2") (pintype "passive"))
    )
    (net (code "26") (name "N$643") (class "Default")
      (node (ref "J2") (pin "14") (pinfunction "14_14") (pintype "bidirectional"))
      (node (ref "R107") (pin "2") (pinfunction "2_2") (pintype "passive"))
    )
    (net (code "27") (name "N$644") (class "Default")
      (node (ref "J2") (pin "12") (pinfunction "12_12") (pintype "bidirectional"))
      (node (ref "R105") (pin "2") (pinfunction "2_2") (pintype "passive"))
    )
    (net (code "28") (name "N$710") (class "Default")
      (node (ref "Q6") (pin "C") (pinfunction "C_C") (pintype "passive"))
    )
    (net (code "29") (name "N$719") (class "Default")
      (node (ref "Q10") (pin "C") (pinfunction "C_C") (pintype "passive"))
    )
    (net (code "30") (name "N$724") (class "Default")
      (node (ref "Q8") (pin "C") (pinfunction "C_C") (pintype "passive"))
    )
    (net (code "31") (name "NORMHIGH1") (class "Default")
      (node (ref "C9") (pin "+") (pinfunction "1_+") (pintype "passive"))
      (node (ref "J1") (pin "1") (pinfunction "1_1") (pintype "bidirectional"))
    )
    (net (code "32") (name "NORMHIGH2") (class "Default")
      (node (ref "C5") (pin "+") (pinfunction "1_+") (pintype "passive"))
      (node (ref "J1") (pin "2") (pinfunction "2_2") (pintype "bidirectional"))
    )
    (net (code "33") (name "Net-(C1-1)") (class "Default")
      (node (ref "C1") (pin "+") (pinfunction "1_+") (pintype "passive"))
      (node (ref "D1") (pin "C") (pinfunction "C_C") (pintype "passive"))
      (node (ref "IC3") (pin "13") (pinfunction "-IN_13") (pintype "input"))
      (node (ref "R2") (pin "1") (pinfunction "1_1") (pintype "passive"))
    )
    (net (code "34") (name "Net-(C1-2)") (class "Default")
      (node (ref "C1") (pin "-") (pinfunction "2_-") (pintype "passive"))
      (node (ref "D1") (pin "A") (pinfunction "A_A") (pintype "passive"))
      (node (ref "IC3") (pin "14") (pinfunction "OUT_14") (pintype "output"))
      (node (ref "Q2") (pin "B") (pinfunction "B_B") (pintype "passive"))
    )
    (net (code "35") (name "Net-(C2-1)") (class "Default")
      (node (ref "C2") (pin "+") (pinfunction "1_+") (pintype "passive"))
      (node (ref "D2") (pin "C") (pinfunction "C_C") (pintype "passive"))
      (node (ref "IC1") (pin "2") (pinfunction "-IN_2") (pintype "input"))
      (node (ref "R1") (pin "2") (pinfunction "2_2") (pintype "passive"))
      (node (ref "R5") (pin "1") (pinfunction "1_1") (pintype "passive"))
    )
    (net (code "36") (name "Net-(C2-2)") (class "Default")
      (node (ref "C2") (pin "-") (pinfunction "2_-") (pintype "passive"))
      (node (ref "D2") (pin "A") (pinfunction "A_A") (pintype "passive"))
      (node (ref "IC1") (pin "6") (pinfunction "OUT_6") (pintype "output"))
      (node (ref "Q1") (pin "B") (pinfunction "B_B") (pintype "passive"))
      (node (ref "Q1") (pin "E") (pinfunction "E_E") (pintype "passive"))
      (node (ref "R11") (pin "1") (pinfunction "1_1") (pintype "passive"))
      (node (ref "R5") (pin "2") (pinfunction "2_2") (pintype "passive"))
    )
    (net (code "37") (name "Net-(C3-1)") (class "Default")
      (node (ref "C3") (pin "+") (pinfunction "1_+") (pintype "passive"))
      (node (ref "IC3") (pin "2") (pinfunction "-IN_2") (pintype "input"))
      (node (ref "R12") (pin "2") (pinfunction "2_2") (pintype "passive"))
      (node (ref "R13") (pin "2") (pinfunction "2_2") (pintype "passive"))
      (node (ref "R14") (pin "2") (pinfunction "2_2") (pintype "passive"))
      (node (ref "R15") (pin "2") (pinfunction "2_2") (pintype "passive"))
      (node (ref "R20") (pin "1") (pinfunction "A_1") (pintype "passive"))
    )
    (net (code "38") (name "Net-(C3-2)") (class "Default")
      (node (ref "C3") (pin "-") (pinfunction "2_-") (pintype "passive"))
      (node (ref "IC3") (pin "1") (pinfunction "OUT_1") (pintype "output"))
      (node (ref "R22") (pin "1") (pinfunction "1_1") (pintype "passive"))
      (node (ref "R25") (pin "1") (pinfunction "1_1") (pintype "passive"))
    )
    (net (code "39") (name "Net-(C6-2)") (class "Default")
      (node (ref "C6") (pin "-") (pinfunction "2_-") (pintype "passive"))
      (node (ref "IC3") (pin "7") (pinfunction "OUT_7") (pintype "output"))
      (node (ref "R33") (pin "2") (pinfunction "2_2") (pintype "passive"))
    )
    (net (code "40") (name "Net-(C7-1)") (class "Default")
      (node (ref "C7") (pin "+") (pinfunction "1_+") (pintype "passive"))
      (node (ref "IC3") (pin "9") (pinfunction "-IN_9") (pintype "input"))
      (node (ref "IC6") (pin "6") (pinfunction "C2_6") (pintype "passive"))
      (node (ref "R42") (pin "1") (pinfunction "1_1") (pintype "passive"))
    )
    (net (code "41") (name "Net-(C14-1)") (class "Default")
      (node (ref "C14") (pin "+") (pinfunction "1_+") (pintype "passive"))
      (node (ref "R98") (pin "2") (pinfunction "2_2") (pintype "passive"))
    )
    (net (code "42") (name "Net-(C15-2)") (class "Default")
      (node (ref "C15") (pin "-") (pinfunction "2_-") (pintype "passive"))
      (node (ref "IC24") (pin "7") (pinfunction "OUT_7") (pintype "output"))
      (node (ref "R103") (pin "1") (pinfunction "A_1") (pintype "passive"))
      (node (ref "R106") (pin "1") (pinfunction "1_1") (pintype "passive"))
    )
    (net (code "43") (name "Net-(C16-2)") (class "Default")
      (node (ref "C16") (pin "-") (pinfunction "2_-") (pintype "passive"))
      (node (ref "IC24") (pin "1") (pinfunction "OUT_1") (pintype "output"))
      (node (ref "R104") (pin "1") (pinfunction "A_1") (pintype "passive"))
      (node (ref "R107") (pin "1") (pinfunction "1_1") (pintype "passive"))
    )
    (net (code "44") (name "Net-(D10-PadC)") (class "Default")
      (node (ref "D10") (pin "C") (pinfunction "C_C") (pintype "passive"))
      (node (ref "D11") (pin "A") (pinfunction "A_A") (pintype "passive"))
    )
    (net (code "45") (name "Net-(D11-PadC)") (class "Default")
      (node (ref "D11") (pin "C") (pinfunction "C_C") (pintype "passive"))
      (node (ref "D12") (pin "A") (pinfunction "A_A") (pintype "passive"))
    )
    (net (code "46") (name "Net-(D13-PadA)") (class "Default")
      (node (ref "D13") (pin "A") (pinfunction "A_A") (pintype "passive"))
      (node (ref "D14") (pin "C") (pinfunction "C_C") (pintype "passive"))
    )
    (net (code "47") (name "Net-(D14-PadA)") (class "Default")
      (node (ref "D14") (pin "A") (pinfunction "A_A") (pintype "passive"))
      (node (ref "D15") (pin "C") (pinfunction "C_C") (pintype "passive"))
    )
    (net (code "48") (name "Net-(D16-PadC)") (class "Default")
      (node (ref "D16") (pin "C") (pinfunction "C_C") (pintype "passive"))
      (node (ref "D17") (pin "A") (pinfunction "A_A") (pintype "passive"))
    )
    (net (code "49") (name "Net-(D17-PadC)") (class "Default")
      (node (ref "D17") (pin "C") (pinfunction "C_C") (pintype "passive"))
      (node (ref "D18") (pin "A") (pinfunction "A_A") (pintype "passive"))
    )
    (net (code "50") (name "Net-(D19-PadA)") (class "Default")
      (node (ref "D19") (pin "A") (pinfunction "A_A") (pintype "passive"))
      (node (ref "D20") (pin "C") (pinfunction "C_C") (pintype "passive"))
    )
    (net (code "51") (name "Net-(D20-PadA)") (class "Default")
      (node (ref "D20") (pin "A") (pinfunction "A_A") (pintype "passive"))
      (node (ref "D21") (pin "C") (pinfunction "C_C") (pintype "passive"))
    )
    (net (code "52") (name "Net-(IC2A--IN)") (class "Default")
      (node (ref "IC2") (pin "4") (pinfunction "-IN_4") (pintype "bidirectional"))
      (node (ref "R16") (pin "2") (pinfunction "2_2") (pintype "passive"))
      (node (ref "R18") (pin "1") (pinfunction "1_1") (pintype "passive"))
      (node (ref "R19") (pin "1") (pinfunction "1_1") (pintype "passive"))
    )
    (net (code "53") (name "Net-(IC2A-ABC+)") (class "Default")
      (node (ref "IC2") (pin "1") (pinfunction "ABC+_1") (pintype "bidirectional"))
      (node (ref "R17") (pin "1") (pinfunction "1_1") (pintype "passive"))
    )
    (net (code "54") (name "Net-(IC2A-BI)") (class "Default")
      (node (ref "IC2") (pin "7") (pinfunction "BI_7") (pintype "bidirectional"))
      (node (ref "IC2") (pin "8") (pinfunction "BO_8") (pintype "bidirectional"))
    )
    (net (code "55") (name "Net-(IC2A-IN+)") (class "Default")
      (node (ref "IC2") (pin "3") (pinfunction "IN+_3") (pintype "bidirectional"))
      (node (ref "R3") (pin "2") (pinfunction "2_2") (pintype "passive"))
      (node (ref "R6") (pin "2") (pinfunction "2_2") (pintype "passive"))
    )
    (net (code "56") (name "Net-(IC2B--IN)") (class "Default")
      (node (ref "IC2") (pin "13") (pinfunction "-IN_13") (pintype "bidirectional"))
      (node (ref "R38") (pin "2") (pinfunction "2_2") (pintype "passive"))
    )
    (net (code "57") (name "Net-(IC2B-ABC+)") (class "Default")
      (node (ref "IC2") (pin "16") (pinfunction "ABC+_16") (pintype "bidirectional"))
      (node (ref "R39") (pin "1") (pinfunction "1_1") (pintype "passive"))
    )
    (net (code "58") (name "Net-(IC2B-BI)") (class "Default")
      (node (ref "IC2") (pin "10") (pinfunction "BI_10") (pintype "bidirectional"))
      (node (ref "IC2") (pin "9") (pinfunction "BO_9") (pintype "bidirectional"))
    )
    (net (code "59") (name "Net-(IC2B-IN+)") (class "Default")
      (node (ref "IC2") (pin "14") (pinfunction "IN+_14") (pintype "bidirectional"))
      (node (ref "R34") (pin "2") (pinfunction "2_2") (pintype "passive"))
      (node (ref "R35") (pin "2") (pinfunction "2_2") (pintype "passive"))
    )
    (net (code "60") (name "Net-(IC4B--IN)") (class "Default")
      (node (ref "IC4") (pin "6") (pinfunction "-IN_6") (pintype "input"))
      (node (ref "IC4") (pin "7") (pinfunction "OUT_7") (pintype "output"))
      (node (ref "R29") (pin "2") (pinfunction "2_2") (pintype "passive"))
      (node (ref "R31") (pin "2") (pinfunction "2_2") (pintype "passive"))
      (node (ref "R37") (pin "1") (pinfunction "1_1") (pintype "passive"))
    )
    (net (code "61") (name "Net-(IC5A--IN)") (class "Default")
      (node (ref "IC5") (pin "4") (pinfunction "-IN_4") (pintype "bidirectional"))
      (node (ref "R28") (pin "2") (pinfunction "2_2") (pintype "passive"))
      (node (ref "R29") (pin "1") (pinfunction "1_1") (pintype "passive"))
      (node (ref "R30") (pin "1") (pinfunction "1_1") (pintype "passive"))
    )
    (net (code "62") (name "Net-(IC5A-ABC+)") (class "Default")
      (node (ref "IC5") (pin "1") (pinfunction "ABC+_1") (pintype "bidirectional"))
      (node (ref "R23") (pin "1") (pinfunction "1_1") (pintype "passive"))
    )
    (net (code "63") (name "Net-(IC5A-BI)") (class "Default")
      (node (ref "IC5") (pin "7") (pinfunction "BI_7") (pintype "bidirectional"))
      (node (ref "IC5") (pin "8") (pinfunction "BO_8") (pintype "bidirectional"))
    )
    (net (code "64") (name "Net-(IC5A-IN+)") (class "Default")
      (node (ref "IC5") (pin "3") (pinfunction "IN+_3") (pintype "bidirectional"))
      (node (ref "R24") (pin "2") (pinfunction "2_2") (pintype "passive"))
      (node (ref "R26") (pin "2") (pinfunction "2_2") (pintype "passive"))
    )
    (net (code "65") (name "Net-(IC5B--IN)") (class "Default")
      (node (ref "IC5") (pin "13") (pinfunction "-IN_13") (pintype "bidirectional"))
      (node (ref "R41") (pin "2") (pinfunction "2_2") (pintype "passive"))
    )
    (net (code "66") (name "Net-(IC5B-ABC+)") (class "Default")
      (node (ref "IC5") (pin "16") (pinfunction "ABC+_16") (pintype "bidirectional"))
      (node (ref "R36") (pin "1") (pinfunction "1_1") (pintype "passive"))
    )
    (net (code "67") (name "Net-(IC5B-BI)") (class "Default")
      (node (ref "IC5") (pin "10") (pinfunction "BI_10") (pintype "bidirectional"))
      (node (ref "IC5") (pin "9") (pinfunction "BO_9") (pintype "bidirectional"))
    )
    (net (code "68") (name "Net-(IC5B-IN+)") (class "Default")
      (node (ref "IC5") (pin "14") (pinfunction "IN+_14") (pintype "bidirectional"))
      (node (ref "R37") (pin "2") (pinfunction "2_2") (pintype "passive"))
      (node (ref "R40") (pin "2") (pinfunction "2_2") (pintype "passive"))
    )
    (net (code "69") (name "Net-(IC6-B1)") (class "Default")
      (node (ref "IC6") (pin "2") (pinfunction "B1_2") (pintype "passive"))
      (node (ref "R25") (pin "2") (pinfunction "2_2") (pintype "passive"))
      (node (ref "R32") (pin "2") (pinfunction "2_2") (pintype "passive"))
    )
    (net (code "70") (name "Net-(IC6-E1)") (class "Default")
      (node (ref "IC6") (pin "3") (pinfunction "E1_3") (pintype "passive"))
      (node (ref "IC6") (pin "4") (pinfunction "E2_4") (pintype "passive"))
      (node (ref "R33") (pin "1") (pinfunction "1_1") (pintype "passive"))
    )
    (net (code "71") (name "Net-(IC7A--IN)") (class "Default")
      (node (ref "D7") (pin "C") (pinfunction "C_C") (pintype "passive"))
      (node (ref "IC7") (pin "2") (pinfunction "-IN_2") (pintype "input"))
      (node (ref "R45") (pin "1") (pinfunction "1_1") (pintype "passive"))
    )
    (net (code "72") (name "Net-(IC7A-OUT)") (class "Default")
      (node (ref "D7") (pin "A") (pinfunction "A_A") (pintype "passive"))
      (node (ref "IC7") (pin "1") (pinfunction "OUT_1") (pintype "output"))
      (node (ref "Q3") (pin "B") (pinfunction "B_B") (pintype "passive"))
      (node (ref "Q5") (pin "B") (pinfunction "B_B") (pintype "passive"))
    )
    (net (code "73") (name "Net-(IC7B--IN)") (class "Default")
      (node (ref "IC7") (pin "6") (pinfunction "-IN_6") (pintype "input"))
      (node (ref "R44") (pin "2") (pinfunction "2_2") (pintype "passive"))
      (node (ref "R46") (pin "1") (pinfunction "1_1") (pintype "passive"))
    )
    (net (code "74") (name "Net-(IC7B-OUT)") (class "Default")
      (node (ref "IC7") (pin "7") (pinfunction "OUT_7") (pintype "output"))
      (node (ref "Q4") (pin "B") (pinfunction "B_B") (pintype "passive"))
      (node (ref "Q6") (pin "B") (pinfunction "B_B") (pintype "passive"))
    )
    (net (code "75") (name "Net-(IC7C--IN)") (class "Default")
      (node (ref "D9") (pin "C") (pinfunction "C_C") (pintype "passive"))
      (node (ref "IC7") (pin "13") (pinfunction "-IN_13") (pintype "input"))
      (node (ref "R54") (pin "2") (pinfunction "2_2") (pintype "passive"))
      (node (ref "R58") (pin "1") (pinfunction "1_1") (pintype "passive"))
    )
    (net (code "76") (name "Net-(IC7C-OUT)") (class "Default")
      (node (ref "D9") (pin "A") (pinfunction "A_A") (pintype "passive"))
      (node (ref "IC7") (pin "14") (pinfunction "OUT_14") (pintype "output"))
      (node (ref "Q10") (pin "B") (pinfunction "B_B") (pintype "passive"))
      (node (ref "Q9") (pin "B") (pinfunction "B_B") (pintype "passive"))
    )
    (net (code "77") (name "Net-(IC7D--IN)") (class "Default")
      (node (ref "D8") (pin "C") (pinfunction "C_C") (pintype "passive"))
      (node (ref "IC7") (pin "9") (pinfunction "-IN_9") (pintype "input"))
      (node (ref "R55") (pin "1") (pinfunction "1_1") (pintype "passive"))
    )
    (net (code "78") (name "Net-(IC7D-OUT)") (class "Default")
      (node (ref "D8") (pin "A") (pinfunction "A_A") (pintype "passive"))
      (node (ref "IC7") (pin "8") (pinfunction "OUT_8") (pintype "output"))
      (node (ref "Q7") (pin "B") (pinfunction "B_B") (pintype "passive"))
      (node (ref "Q8") (pin "B") (pinfunction "B_B") (pintype "passive"))
    )
    (net (code "79") (name "Net-(IC8A--IN)") (class "Default")
      (node (ref "IC8") (pin "4") (pinfunction "-IN_4") (pintype "bidirectional"))
      (node (ref "R69") (pin "1") (pinfunction "1_1") (pintype "passive"))
    )
    (net (code "80") (name "Net-(IC8A-ABC+)") (class "Default")
      (node (ref "IC8") (pin "1") (pinfunction "ABC+_1") (pintype "bidirectional"))
      (node (ref "R75") (pin "1") (pinfunction "1_1") (pintype "passive"))
    )
    (net (code "81") (name "Net-(IC8A-BI)") (class "Default")
      (node (ref "IC8") (pin "7") (pinfunction "BI_7") (pintype "bidirectional"))
      (node (ref "IC8") (pin "8") (pinfunction "BO_8") (pintype "bidirectional"))
    )
    (net (code "82") (name "Net-(IC8A-DI)") (class "Default")
      (node (ref "IC8") (pin "2") (pinfunction "DI_2") (pintype "bidirectional"))
      (node (ref "R68") (pin "1") (pinfunction "1_1") (pintype "passive"))
    )
    (net (code "83") (name "Net-(IC8A-IN+)") (class "Default")
      (node (ref "IC8") (pin "3") (pinfunction "IN+_3") (pintype "bidirectional"))
      (node (ref "R66") (pin "1") (pinfunction "1_1") (pintype "passive"))
      (node (ref "R67") (pin "1") (pinfunction "1_1") (pintype "passive"))
    )
    (net (code "84") (name "Net-(IC8B--IN)") (class "Default")
      (node (ref "IC8") (pin "13") (pinfunction "-IN_13") (pintype "bidirectional"))
      (node (ref "R72") (pin "1") (pinfunction "1_1") (pintype "passive"))
      (node (ref "R73") (pin "1") (pinfunction "1_1") (pintype "passive"))
    )
    (net (code "85") (name "Net-(IC8B-ABC+)") (class "Default")
      (node (ref "IC8") (pin "16") (pinfunction "ABC+_16") (pintype "bidirectional"))
      (node (ref "R74") (pin "1") (pinfunction "1_1") (pintype "passive"))
    )
    (net (code "86") (name "Net-(IC8B-BI)") (class "Default")
      (node (ref "IC8") (pin "10") (pinfunction "BI_10") (pintype "bidirectional"))
      (node (ref "IC8") (pin "9") (pinfunction "BO_9") (pintype "bidirectional"))
    )
    (net (code "87") (name "Net-(IC8B-DI)") (class "Default")
      (node (ref "IC8") (pin "15") (pinfunction "DI_15") (pintype "bidirectional"))
      (node (ref "R71") (pin "1") (pinfunction "1_1") (pintype "passive"))
    )
    (net (code "88") (name "Net-(IC8B-IN+)") (class "Default")
      (node (ref "IC8") (pin "14") (pinfunction "IN+_14") (pintype "bidirectional"))
      (node (ref "R70") (pin "1") (pinfunction "1_1") (pintype "passive"))
    )
    (net (code "89") (name "Net-(IC9A--IN)") (class "Default")
      (node (ref "IC9") (pin "4") (pinfunction "-IN_4") (pintype "bidirectional"))
      (node (ref "R81") (pin "1") (pinfunction "1_1") (pintype "passive"))
    )
    (net (code "90") (name "Net-(IC9A-ABC+)") (class "Default")
      (node (ref "IC9") (pin "1") (pinfunction "ABC+_1") (pintype "bidirectional"))
      (node (ref "R87") (pin "1") (pinfunction "1_1") (pintype "passive"))
    )
    (net (code "91") (name "Net-(IC9A-BI)") (class "Default")
      (node (ref "IC9") (pin "7") (pinfunction "BI_7") (pintype "bidirectional"))
      (node (ref "IC9") (pin "8") (pinfunction "BO_8") (pintype "bidirectional"))
    )
    (net (code "92") (name "Net-(IC9A-DI)") (class "Default")
      (node (ref "IC9") (pin "2") (pinfunction "DI_2") (pintype "bidirectional"))
      (node (ref "R80") (pin "1") (pinfunction "1_1") (pintype "passive"))
    )
    (net (code "93") (name "Net-(IC9A-IN+)") (class "Default")
      (node (ref "IC9") (pin "3") (pinfunction "IN+_3") (pintype "bidirectional"))
      (node (ref "R76") (pin "1") (pinfunction "1_1") (pintype "passive"))
      (node (ref "R79") (pin "1") (pinfunction "1_1") (pintype "passive"))
    )
    (net (code "94") (name "Net-(IC9B--IN)") (class "Default")
      (node (ref "IC9") (pin "13") (pinfunction "-IN_13") (pintype "bidirectional"))
      (node (ref "R84") (pin "1") (pinfunction "1_1") (pintype "passive"))
      (node (ref "R85") (pin "1") (pinfunction "1_1") (pintype "passive"))
    )
    (net (code "95") (name "Net-(IC9B-ABC+)") (class "Default")
      (node (ref "IC9") (pin "16") (pinfunction "ABC+_16") (pintype "bidirectional"))
      (node (ref "R86") (pin "1") (pinfunction "1_1") (pintype "passive"))
    )
    (net (code "96") (name "Net-(IC9B-BI)") (class "Default")
      (node (ref "IC9") (pin "10") (pinfunction "BI_10") (pintype "bidirectional"))
      (node (ref "IC9") (pin "9") (pinfunction "BO_9") (pintype "bidirectional"))
    )
    (net (code "97") (name "Net-(IC9B-DI)") (class "Default")
      (node (ref "IC9") (pin "15") (pinfunction "DI_15") (pintype "bidirectional"))
      (node (ref "R83") (pin "1") (pinfunction "1_1") (pintype "passive"))
    )
    (net (code "98") (name "Net-(IC9B-IN+)") (class "Default")
      (node (ref "IC9") (pin "14") (pinfunction "IN+_14") (pintype "bidirectional"))
      (node (ref "R82") (pin "1") (pinfunction "1_1") (pintype "passive"))
    )
    (net (code "99") (name "Net-(IC10C-+IN)") (class "Default")
      (node (ref "IC10") (pin "10") (pinfunction "+IN_10") (pintype "input"))
      (node (ref "R94") (pin "1") (pinfunction "1_1") (pintype "passive"))
      (node (ref "R95") (pin "2") (pinfunction "2_2") (pintype "passive"))
    )
    (net (code "100") (name "Net-(IC10D-+IN)") (class "Default")
      (node (ref "IC10") (pin "12") (pinfunction "+IN_12") (pintype "input"))
      (node (ref "R96") (pin "1") (pinfunction "1_1") (pintype "passive"))
      (node (ref "R97") (pin "2") (pinfunction "2_2") (pintype "passive"))
    )
    (net (code "101") (name "Net-(IC22A-+IN)") (class "Default")
      (node (ref "D10") (pin "A") (pinfunction "A_A") (pintype "passive"))
      (node (ref "D13") (pin "C") (pinfunction "C_C") (pintype "passive"))
      (node (ref "IC22") (pin "3") (pinfunction "+IN_3") (pintype "input"))
      (node (ref "R90") (pin "2") (pinfunction "2_2") (pintype "passive"))
      (node (ref "R92") (pin "2") (pinfunction "2_2") (pintype "passive"))
    )
    (net (code "102") (name "Net-(IC22B-+IN)") (class "Default")
      (node (ref "D16") (pin "A") (pinfunction "A_A") (pintype "passive"))
      (node (ref "D19") (pin "C") (pinfunction "C_C") (pintype "passive"))
      (node (ref "IC22") (pin "5") (pinfunction "+IN_5") (pintype "input"))
      (node (ref "R91") (pin "2") (pinfunction "2_2") (pintype "passive"))
      (node (ref "R93") (pin "2") (pinfunction "2_2") (pintype "passive"))
    )
    (net (code "103") (name "Net-(IC24C-+IN)") (class "Default")
      (node (ref "IC24") (pin "10") (pinfunction "+IN_10") (pintype "input"))
      (node (ref "R100") (pin "2") (pinfunction "2_2") (pintype "passive"))
      (node (ref "R99") (pin "1") (pinfunction "1_1") (pintype "passive"))
    )
    (net (code "104") (name "Net-(IC24C--IN)") (class "Default")
      (node (ref "IC24") (pin "8") (pinfunction "OUT_8") (pintype "output"))
      (node (ref "IC24") (pin "9") (pinfunction "-IN_9") (pintype "input"))
      (node (ref "R105") (pin "1") (pinfunction "1_1") (pintype "passive"))
    )
    (net (code "105") (name "Net-(J2-Pad1)") (class "Default")
      (node (ref "J2") (pin "1") (pinfunction "1_1") (pintype "bidirectional"))
      (node (ref "R88") (pin "1") (pinfunction "1_1") (pintype "passive"))
    )
    (net (code "106") (name "Net-(J2-Pad2)") (class "Default")
      (node (ref "J2") (pin "2") (pinfunction "2_2") (pintype "bidirectional"))
      (node (ref "R89") (pin "1") (pinfunction "1_1") (pintype "passive"))
    )
    (net (code "107") (name "Net-(J2-Pad5)") (class "Default")
      (node (ref "J2") (pin "5") (pinfunction "5_5") (pintype "bidirectional"))
      (node (ref "R90") (pin "1") (pinfunction "1_1") (pintype "passive"))
    )
    (net (code "108") (name "Net-(J2-Pad6)") (class "Default")
      (node (ref "J2") (pin "6") (pinfunction "6_6") (pintype "bidirectional"))
      (node (ref "R91") (pin "1") (pinfunction "1_1") (pintype "passive"))
    )
    (net (code "109") (name "Net-(Q1-PadC)") (class "Default")
      (node (ref "Q1") (pin "C") (pinfunction "C_C") (pintype "passive"))
      (node (ref "R17") (pin "2") (pinfunction "2_2") (pintype "passive"))
      (node (ref "R39") (pin "2") (pinfunction "2_2") (pintype "passive"))
    )
    (net (code "110") (name "Net-(Q2-PadC)") (class "Default")
      (node (ref "Q2") (pin "C") (pinfunction "C_C") (pintype "passive"))
      (node (ref "R23") (pin "2") (pinfunction "2_2") (pintype "passive"))
      (node (ref "R36") (pin "2") (pinfunction "2_2") (pintype "passive"))
    )
    (net (code "111") (name "Net-(Q2-PadE)") (class "Default")
      (node (ref "Q2") (pin "E") (pinfunction "E_E") (pintype "passive"))
      (node (ref "R10") (pin "2") (pinfunction "2_2") (pintype "passive"))
      (node (ref "R2") (pin "2") (pinfunction "2_2") (pintype "passive"))
    )
    (net (code "112") (name "Net-(Q3-PadE)") (class "Default")
      (node (ref "Q3") (pin "E") (pinfunction "E_E") (pintype "passive"))
      (node (ref "R45") (pin "2") (pinfunction "2_2") (pintype "passive"))
      (node (ref "R48") (pin "1") (pinfunction "1_1") (pintype "passive"))
    )
    (net (code "113") (name "Net-(Q4-PadE)") (class "Default")
      (node (ref "Q4") (pin "E") (pinfunction "E_E") (pintype "passive"))
      (node (ref "R46") (pin "2") (pinfunction "2_2") (pintype "passive"))
      (node (ref "R51") (pin "2") (pinfunction "2_2") (pintype "passive"))
    )
    (net (code "114") (name "Net-(Q5-PadE)") (class "Default")
      (node (ref "Q5") (pin "E") (pinfunction "E_E") (pintype "passive"))
      (node (ref "R52") (pin "1") (pinfunction "1_1") (pintype "passive"))
    )
    (net (code "115") (name "Net-(Q6-PadE)") (class "Default")
      (node (ref "Q6") (pin "E") (pinfunction "E_E") (pintype "passive"))
      (node (ref "R53") (pin "2") (pinfunction "2_2") (pintype "passive"))
    )
    (net (code "116") (name "Net-(Q7-PadE)") (class "Default")
      (node (ref "Q7") (pin "E") (pinfunction "E_E") (pintype "passive"))
      (node (ref "R55") (pin "2") (pinfunction "2_2") (pintype "passive"))
      (node (ref "R57") (pin "1") (pinfunction "1_1") (pintype "passive"))
    )
    (net (code "117") (name "Net-(Q8-PadE)") (class "Default")
      (node (ref "Q8") (pin "E") (pinfunction "E_E") (pintype "passive"))
      (node (ref "R60") (pin "1") (pinfunction "1_1") (pintype "passive"))
    )
    (net (code "118") (name "Net-(Q9-PadE)") (class "Default")
      (node (ref "Q9") (pin "E") (pinfunction "E_E") (pintype "passive"))
      (node (ref "R58") (pin "2") (pinfunction "2_2") (pintype "passive"))
      (node (ref "R61") (pin "1") (pinfunction "1_1") (pintype "passive"))
    )
    (net (code "119") (name "Net-(Q10-PadE)") (class "Default")
      (node (ref "Q10") (pin "E") (pinfunction "E_E") (pintype "passive"))
      (node (ref "R63") (pin "1") (pinfunction "1_1") (pintype "passive"))
    )
    (net (code "120") (name "Net-(R4-E)") (class "Default")
      (node (ref "R3") (pin "1") (pinfunction "1_1") (pintype "passive"))
      (node (ref "R4") (pin "2") (pinfunction "E_2") (pintype "passive"))
    )
    (net (code "121") (name "Net-(R4-S)") (class "Default")
      (node (ref "D3") (pin "A") (pinfunction "A_A") (pintype "passive"))
      (node (ref "D4") (pin "C") (pinfunction "C_C") (pintype "passive"))
      (node (ref "R4") (pin "3") (pinfunction "S_3") (pintype "passive"))
      (node (ref "R9") (pin "1") (pinfunction "1_1") (pintype "passive"))
    )
    (net (code "122") (name "Net-(R7-S)") (class "Default")
      (node (ref "R10") (pin "1") (pinfunction "1_1") (pintype "passive"))
      (node (ref "R7") (pin "3") (pinfunction "S_3") (pintype "passive"))
    )
    (net (code "123") (name "Net-(R20-E)") (class "Default")
      (node (ref "R20") (pin "2") (pinfunction "E_2") (pintype "passive"))
      (node (ref "R22") (pin "2") (pinfunction "2_2") (pintype "passive"))
    )
    (net (code "124") (name "Net-(R21-E)") (class "Default")
      (node (ref "R21") (pin "2") (pinfunction "E_2") (pintype "passive"))
      (node (ref "R24") (pin "1") (pinfunction "1_1") (pintype "passive"))
    )
    (net (code "125") (name "Net-(R21-S)") (class "Default")
      (node (ref "D5") (pin "A") (pinfunction "A_A") (pintype "passive"))
      (node (ref "D6") (pin "C") (pinfunction "C_C") (pintype "passive"))
      (node (ref "R21") (pin "3") (pinfunction "S_3") (pintype "passive"))
      (node (ref "R31") (pin "1") (pinfunction "1_1") (pintype "passive"))
    )
    (net (code "126") (name "Net-(R47-S)") (class "Default")
      (node (ref "R47") (pin "3") (pinfunction "S_3") (pintype "passive"))
      (node (ref "R48") (pin "2") (pinfunction "2_2") (pintype "passive"))
    )
    (net (code "127") (name "Net-(R56-S)") (class "Default")
      (node (ref "R56") (pin "3") (pinfunction "S_3") (pintype "passive"))
      (node (ref "R57") (pin "2") (pinfunction "2_2") (pintype "passive"))
    )
    (net (code "128") (name "Net-(R64-A)") (class "Default")
      (node (ref "R64") (pin "1") (pinfunction "A_1") (pintype "passive"))
      (node (ref "R67") (pin "2") (pinfunction "2_2") (pintype "passive"))
    )
    (net (code "129") (name "Net-(R64-S)") (class "Default")
      (node (ref "R64") (pin "3") (pinfunction "S_3") (pintype "passive"))
      (node (ref "R69") (pin "2") (pinfunction "2_2") (pintype "passive"))
    )
    (net (code "130") (name "Net-(R65-A)") (class "Default")
      (node (ref "R65") (pin "1") (pinfunction "A_1") (pintype "passive"))
      (node (ref "R70") (pin "2") (pinfunction "2_2") (pintype "passive"))
    )
    (net (code "131") (name "Net-(R65-S)") (class "Default")
      (node (ref "R65") (pin "3") (pinfunction "S_3") (pintype "passive"))
      (node (ref "R72") (pin "2") (pinfunction "2_2") (pintype "passive"))
    )
    (net (code "132") (name "Net-(R77-A)") (class "Default")
      (node (ref "R77") (pin "1") (pinfunction "A_1") (pintype "passive"))
      (node (ref "R79") (pin "2") (pinfunction "2_2") (pintype "passive"))
    )
    (net (code "133") (name "Net-(R77-S)") (class "Default")
      (node (ref "R77") (pin "3") (pinfunction "S_3") (pintype "passive"))
      (node (ref "R81") (pin "2") (pinfunction "2_2") (pintype "passive"))
    )
    (net (code "134") (name "Net-(R78-A)") (class "Default")
      (node (ref "R78") (pin "1") (pinfunction "A_1") (pintype "passive"))
      (node (ref "R82") (pin "2") (pinfunction "2_2") (pintype "passive"))
    )
    (net (code "135") (name "Net-(R78-S)") (class "Default")
      (node (ref "R78") (pin "3") (pinfunction "S_3") (pintype "passive"))
      (node (ref "R84") (pin "2") (pinfunction "2_2") (pintype "passive"))
    )
    (net (code "136") (name "Net-(R98-Pad1)") (class "Default")
      (node (ref "R98") (pin "1") (pinfunction "1_1") (pintype "passive"))
      (node (ref "R99") (pin "2") (pinfunction "2_2") (pintype "passive"))
    )
    (net (code "137") (name "Net-(R103-E)") (class "Default")
      (node (ref "R101") (pin "2") (pinfunction "2_2") (pintype "passive"))
      (node (ref "R103") (pin "2") (pinfunction "E_2") (pintype "passive"))
    )
    (net (code "138") (name "Net-(R104-E)") (class "Default")
      (node (ref "R102") (pin "2") (pinfunction "2_2") (pintype "passive"))
      (node (ref "R104") (pin "2") (pinfunction "E_2") (pintype "passive"))
    )
    (net (code "139") (name "OSC_X") (class "Default")
      (node (ref "IC4") (pin "1") (pinfunction "OUT_1") (pintype "output"))
      (node (ref "IC4") (pin "2") (pinfunction "-IN_2") (pintype "input"))
      (node (ref "J2") (pin "3") (pinfunction "3_3") (pintype "bidirectional"))
      (node (ref "R18") (pin "2") (pinfunction "2_2") (pintype "passive"))
      (node (ref "R30") (pin "2") (pinfunction "2_2") (pintype "passive"))
      (node (ref "R34") (pin "1") (pinfunction "1_1") (pintype "passive"))
      (node (ref "R9") (pin "2") (pinfunction "2_2") (pintype "passive"))
    )
    (net (code "140") (name "OSC_Y") (class "Default")
      (node (ref "J2") (pin "4") (pinfunction "4_4") (pintype "bidirectional"))
      (node (ref "R19") (pin "2") (pinfunction "2_2") (pintype "passive"))
    )
    (net (code "141") (name "ROUGHTUNE") (class "Default")
      (node (ref "R13") (pin "1") (pinfunction "1_1") (pintype "passive"))
    )
    (net (code "142") (name "X_SUM") (class "Default")
      (node (ref "C15") (pin "+") (pinfunction "1_+") (pintype "passive"))
      (node (ref "IC24") (pin "6") (pinfunction "-IN_6") (pintype "input"))
      (node (ref "IC8") (pin "12") (pinfunction "O_12") (pintype "bidirectional"))
      (node (ref "IC8") (pin "5") (pinfunction "O_5") (pintype "bidirectional"))
      (node (ref "R101") (pin "1") (pinfunction "1_1") (pintype "passive"))
    )
    (net (code "143") (name "Y_SUM") (class "Default")
      (node (ref "C16") (pin "+") (pinfunction "1_+") (pintype "passive"))
      (node (ref "IC24") (pin "2") (pinfunction "-IN_2") (pintype "input"))
      (node (ref "IC9") (pin "12") (pinfunction "O_12") (pintype "bidirectional"))
      (node (ref "IC9") (pin "5") (pinfunction "O_5") (pintype "bidirectional"))
      (node (ref "R102") (pin "1") (pinfunction "1_1") (pintype "passive"))
    )
    (net (code "144") (name "unconnected-(IC2A-DI-Pad2)") (class "Default")
      (node (ref "IC2") (pin "2") (pinfunction "DI_2") (pintype "bidirectional"))
    )
    (net (code "145") (name "unconnected-(IC2B-DI-Pad15)") (class "Default")
      (node (ref "IC2") (pin "15") (pinfunction "DI_15") (pintype "bidirectional"))
    )
    (net (code "146") (name "unconnected-(IC5A-DI-Pad2)") (class "Default")
      (node (ref "IC5") (pin "2") (pinfunction "DI_2") (pintype "bidirectional"))
    )
    (net (code "147") (name "unconnected-(IC5B-DI-Pad15)") (class "Default")
      (node (ref "IC5") (pin "15") (pinfunction "DI_15") (pintype "bidirectional"))
    )
    (net (code "148") (name "unconnected-(J1-Pad3)") (class "Default")
      (node (ref "J1") (pin "3") (pinfunction "3_3") (pintype "bidirectional"))
    )
    (net (code "149") (name "unconnected-(J1-Pad4)") (class "Default")
      (node (ref "J1") (pin "4") (pinfunction "4_4") (pintype "bidirectional"))
    )
    (net (code "150") (name "unconnected-(J1-Pad7)") (class "Default")
      (node (ref "J1") (pin "7") (pinfunction "7_7") (pintype "bidirectional"))
    )
    (net (code "151") (name "unconnected-(J3-Pad13)") (class "Default")
      (node (ref "J3") (pin "13") (pinfunction "13_13") (pintype "bidirectional"))
    )
    (net (code "152") (name "unconnected-(J3-Pad14)") (class "Default")
      (node (ref "J3") (pin "14") (pinfunction "14_14") (pintype "bidirectional"))
    )
    (net (code "153") (name "unconnected-(J3-Pad15)") (class "Default")
      (node (ref "J3") (pin "15") (pinfunction "15_15") (pintype "bidirectional"))
    )
    (net (code "154") (name "unconnected-(J3-Pad16)") (class "Default")
      (node (ref "J3") (pin "16") (pinfunction "16_16") (pintype "bidirectional"))
    )
    (net (code "155") (name "unconnected-(R7-A-Pad1)") (class "Default")
      (node (ref "R7") (pin "1") (pinfunction "A_1") (pintype "passive"))
    )
    (net (code "156") (name "unconnected-(R20-S-Pad3)") (class "Default")
      (node (ref "R20") (pin "3") (pinfunction "S_3") (pintype "passive"))
    )
    (net (code "157") (name "unconnected-(R47-A-Pad1)") (class "Default")
      (node (ref "R47") (pin "1") (pinfunction "A_1") (pintype "passive"))
    )
    (net (code "158") (name "unconnected-(R56-A-Pad1)") (class "Default")
      (node (ref "R56") (pin "1") (pinfunction "A_1") (pintype "passive"))
    )
    (net (code "159") (name "unconnected-(R103-S-Pad3)") (class "Default")
      (node (ref "R103") (pin "3") (pinfunction "S_3") (pintype "passive"))
    )
    (net (code "160") (name "unconnected-(R104-S-Pad3)") (class "Default")
      (node (ref "R104") (pin "3") (pinfunction "S_3") (pintype "passive"))
    )
  )
)
